# xmos_avb_brd_V4.net
KiCad netlist of a schematic drawn in EAGLE
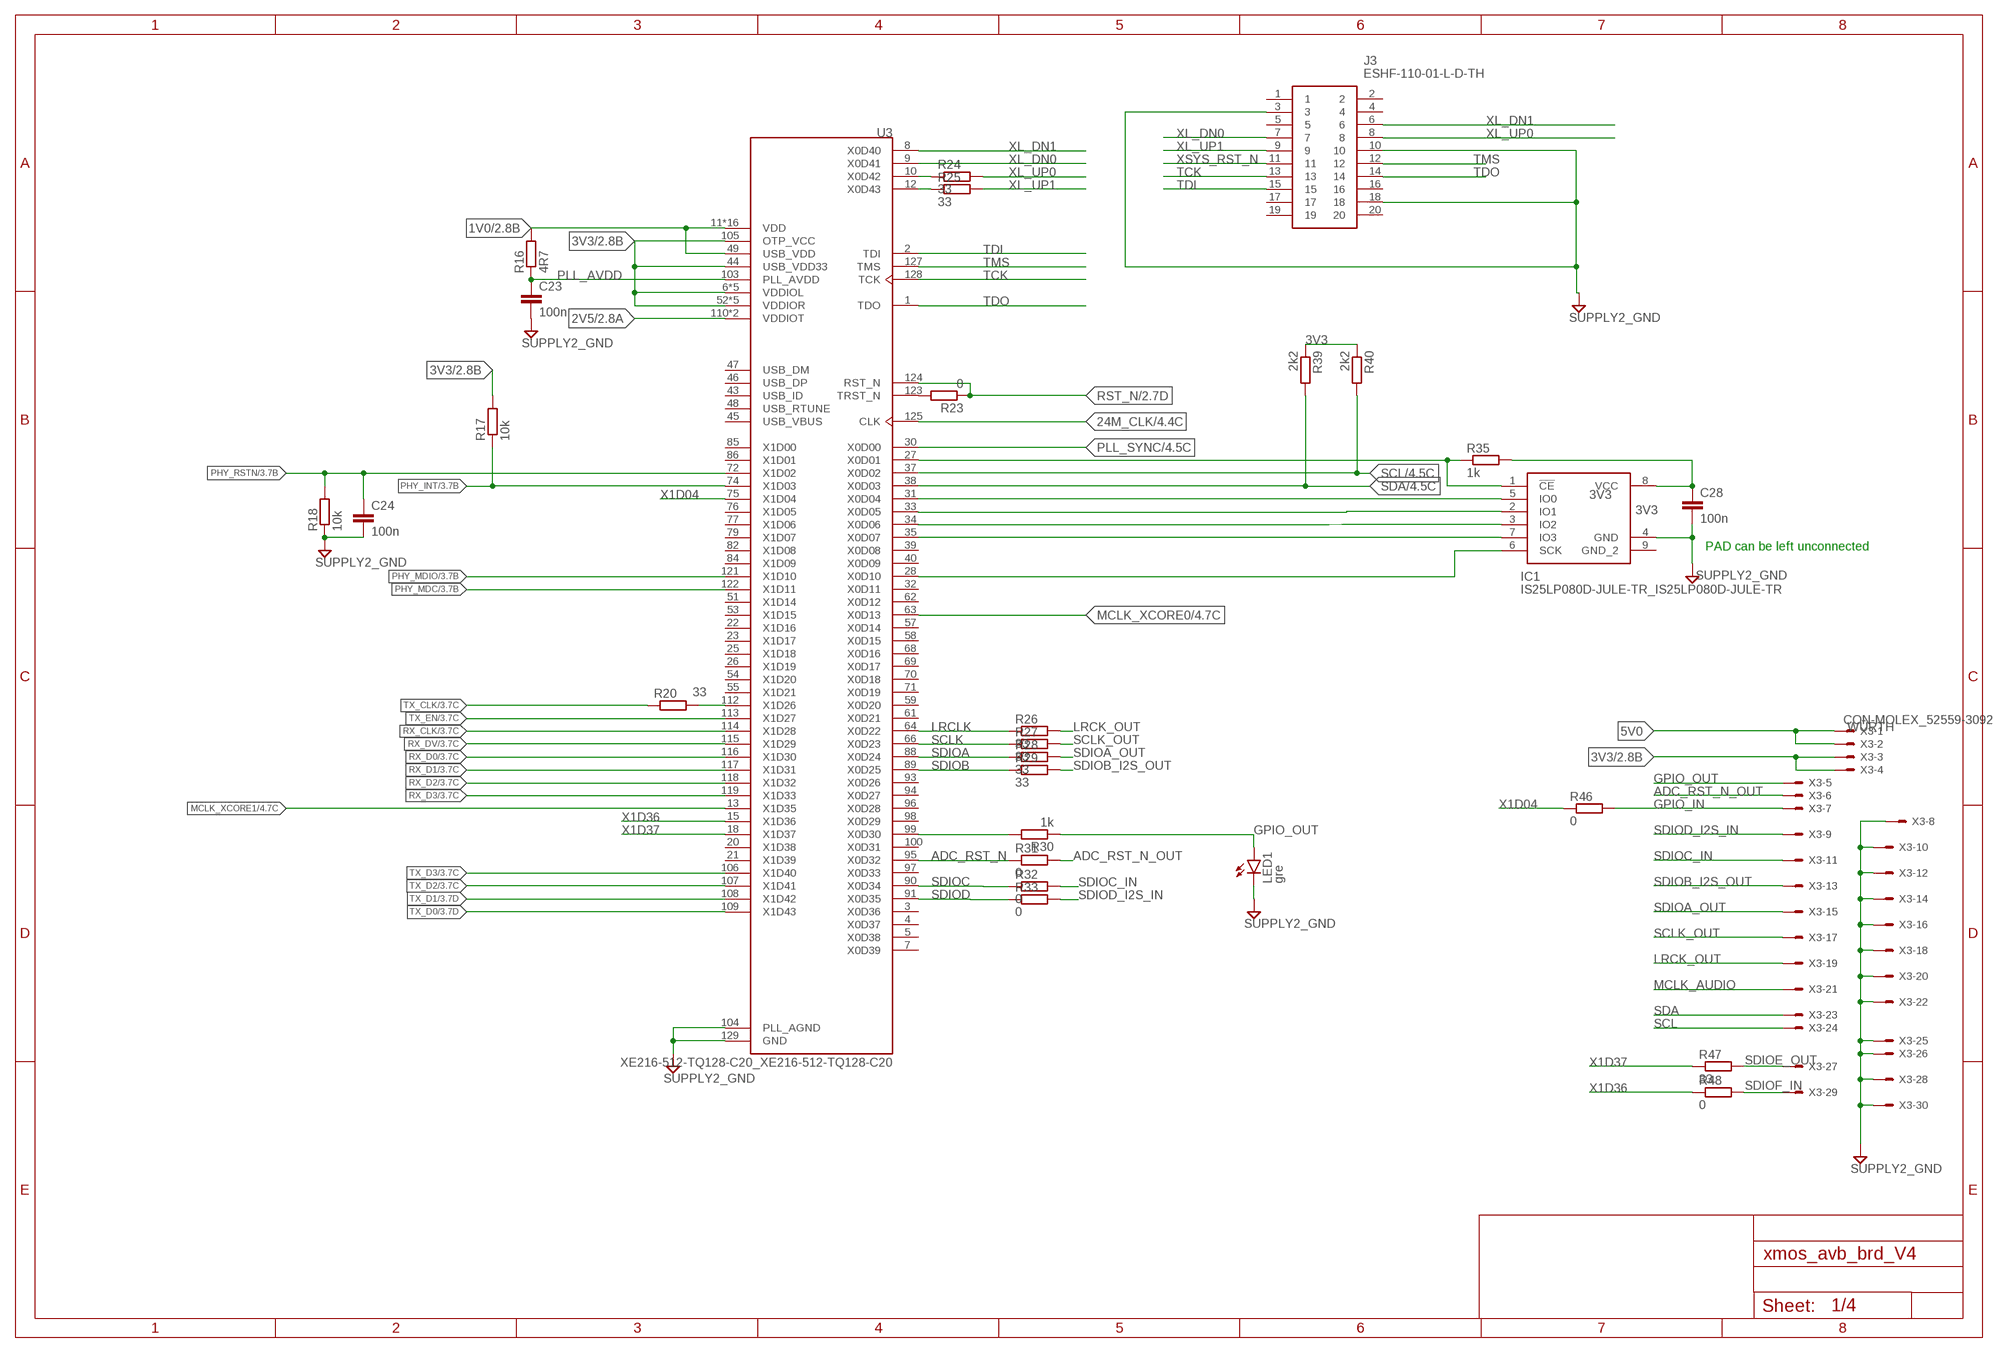
[diagram p0: schematic, sheet 1]
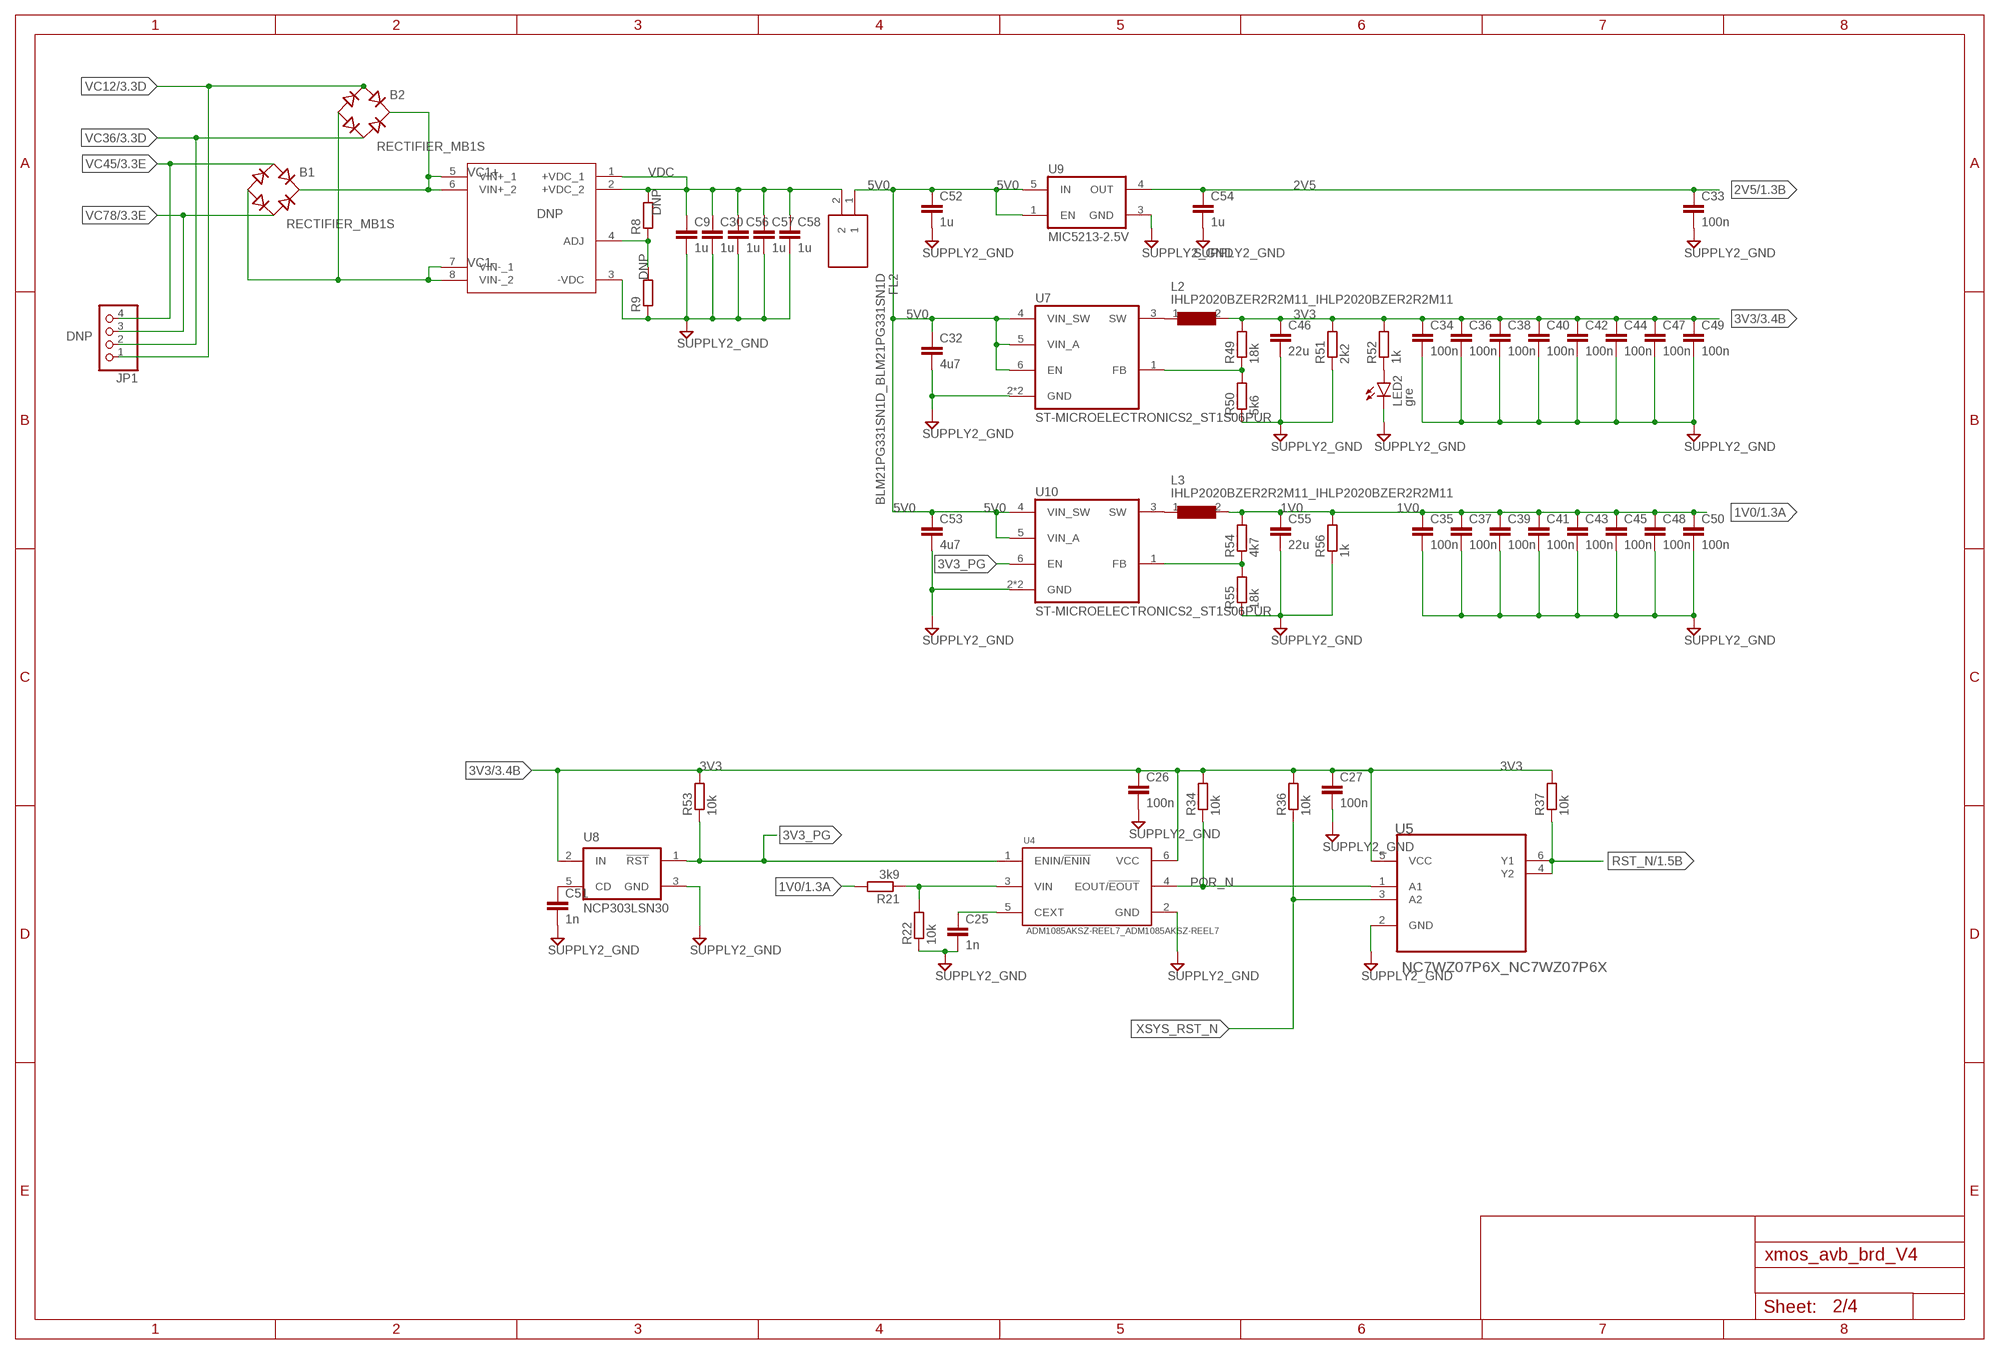
[diagram p1: schematic, sheet 2]
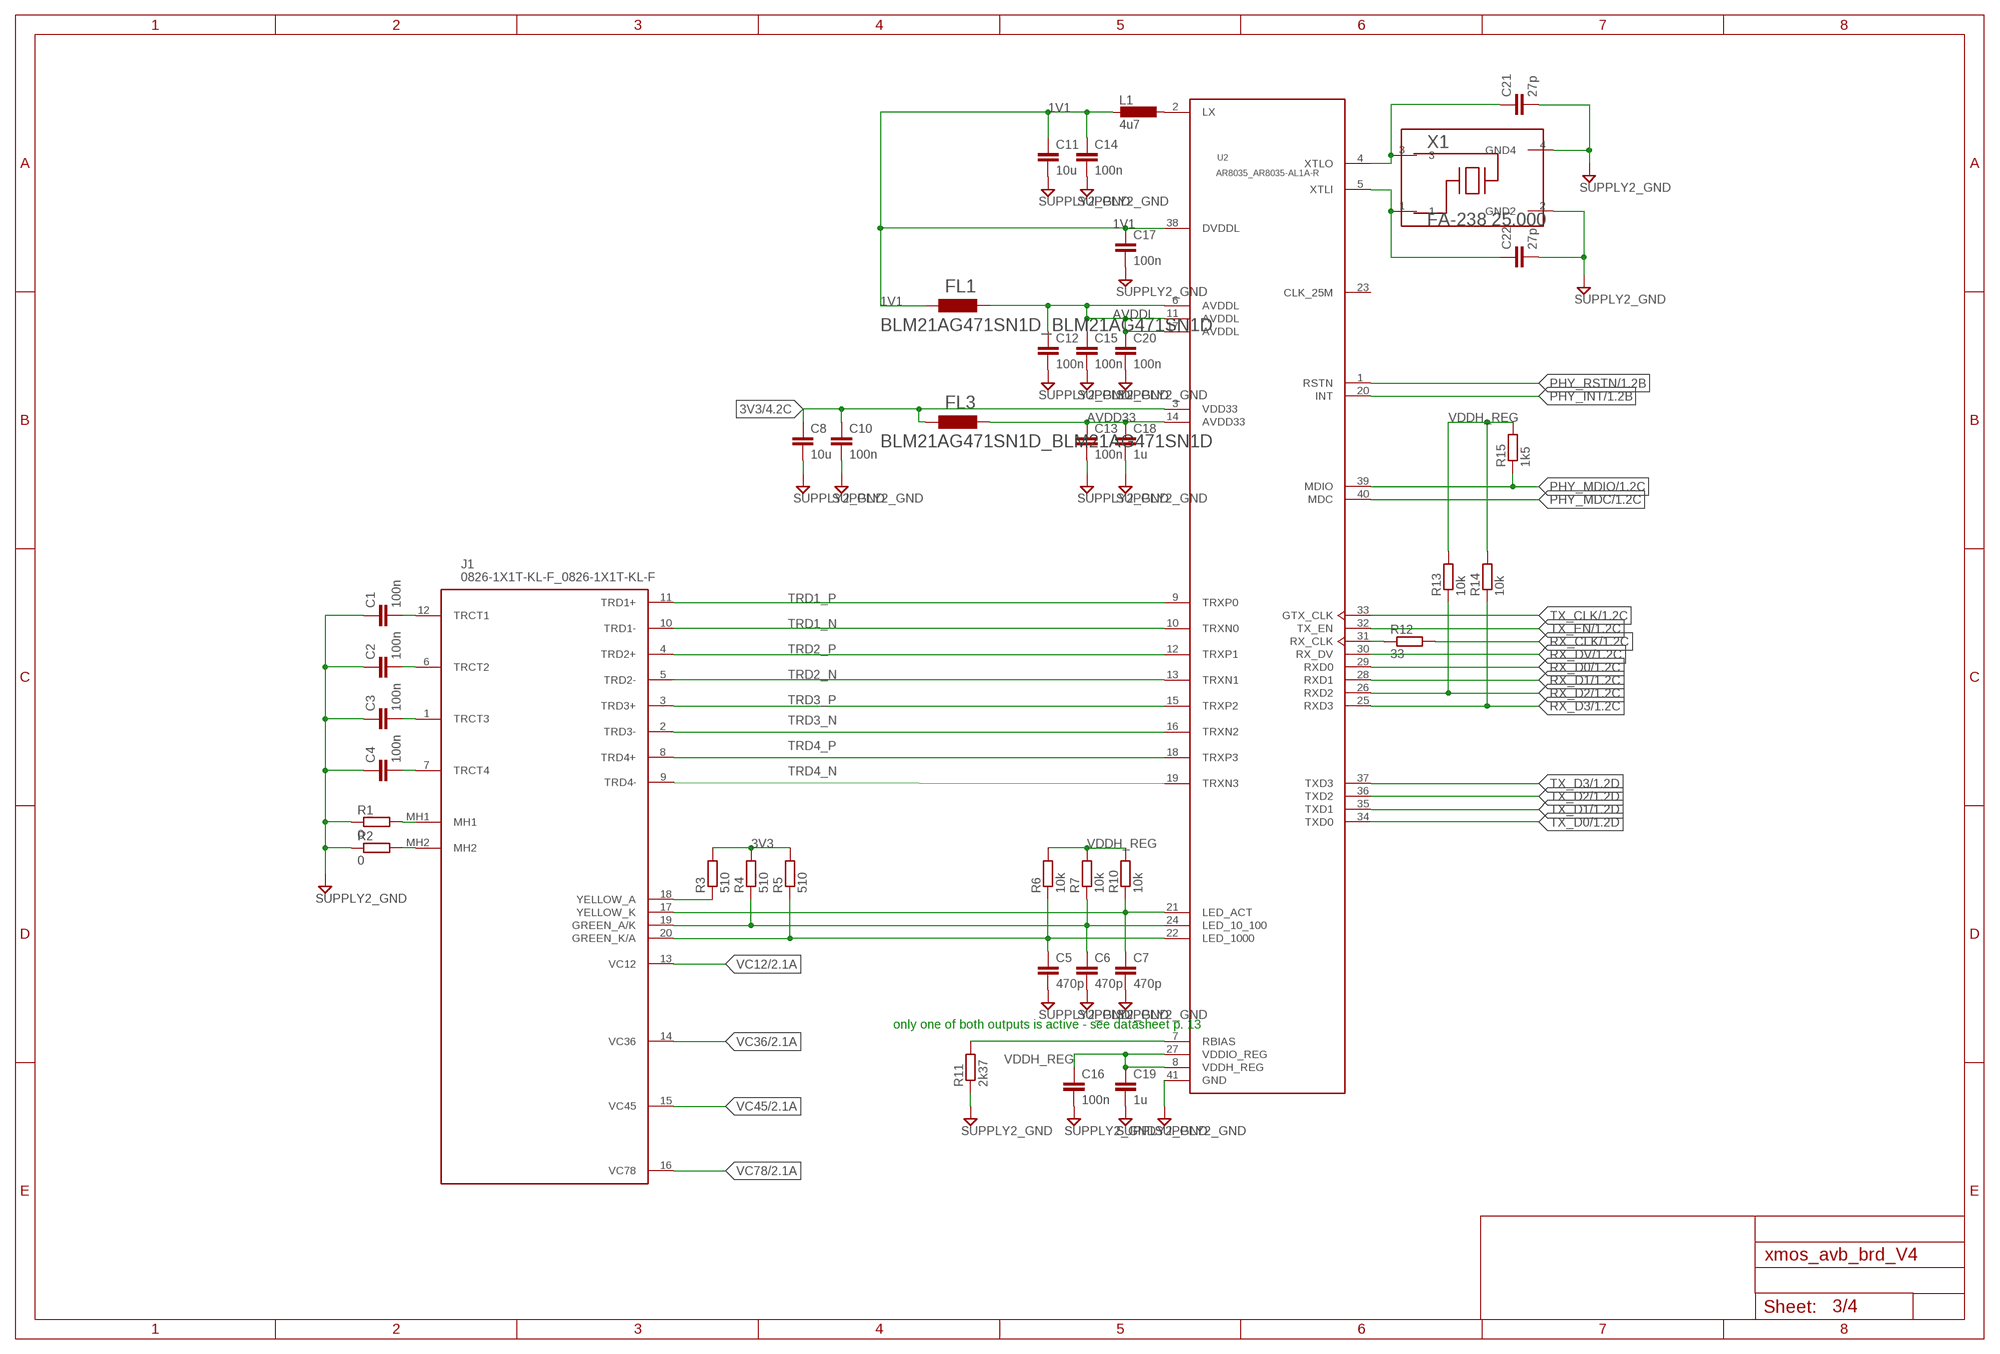
[diagram p2: schematic, sheet 3]
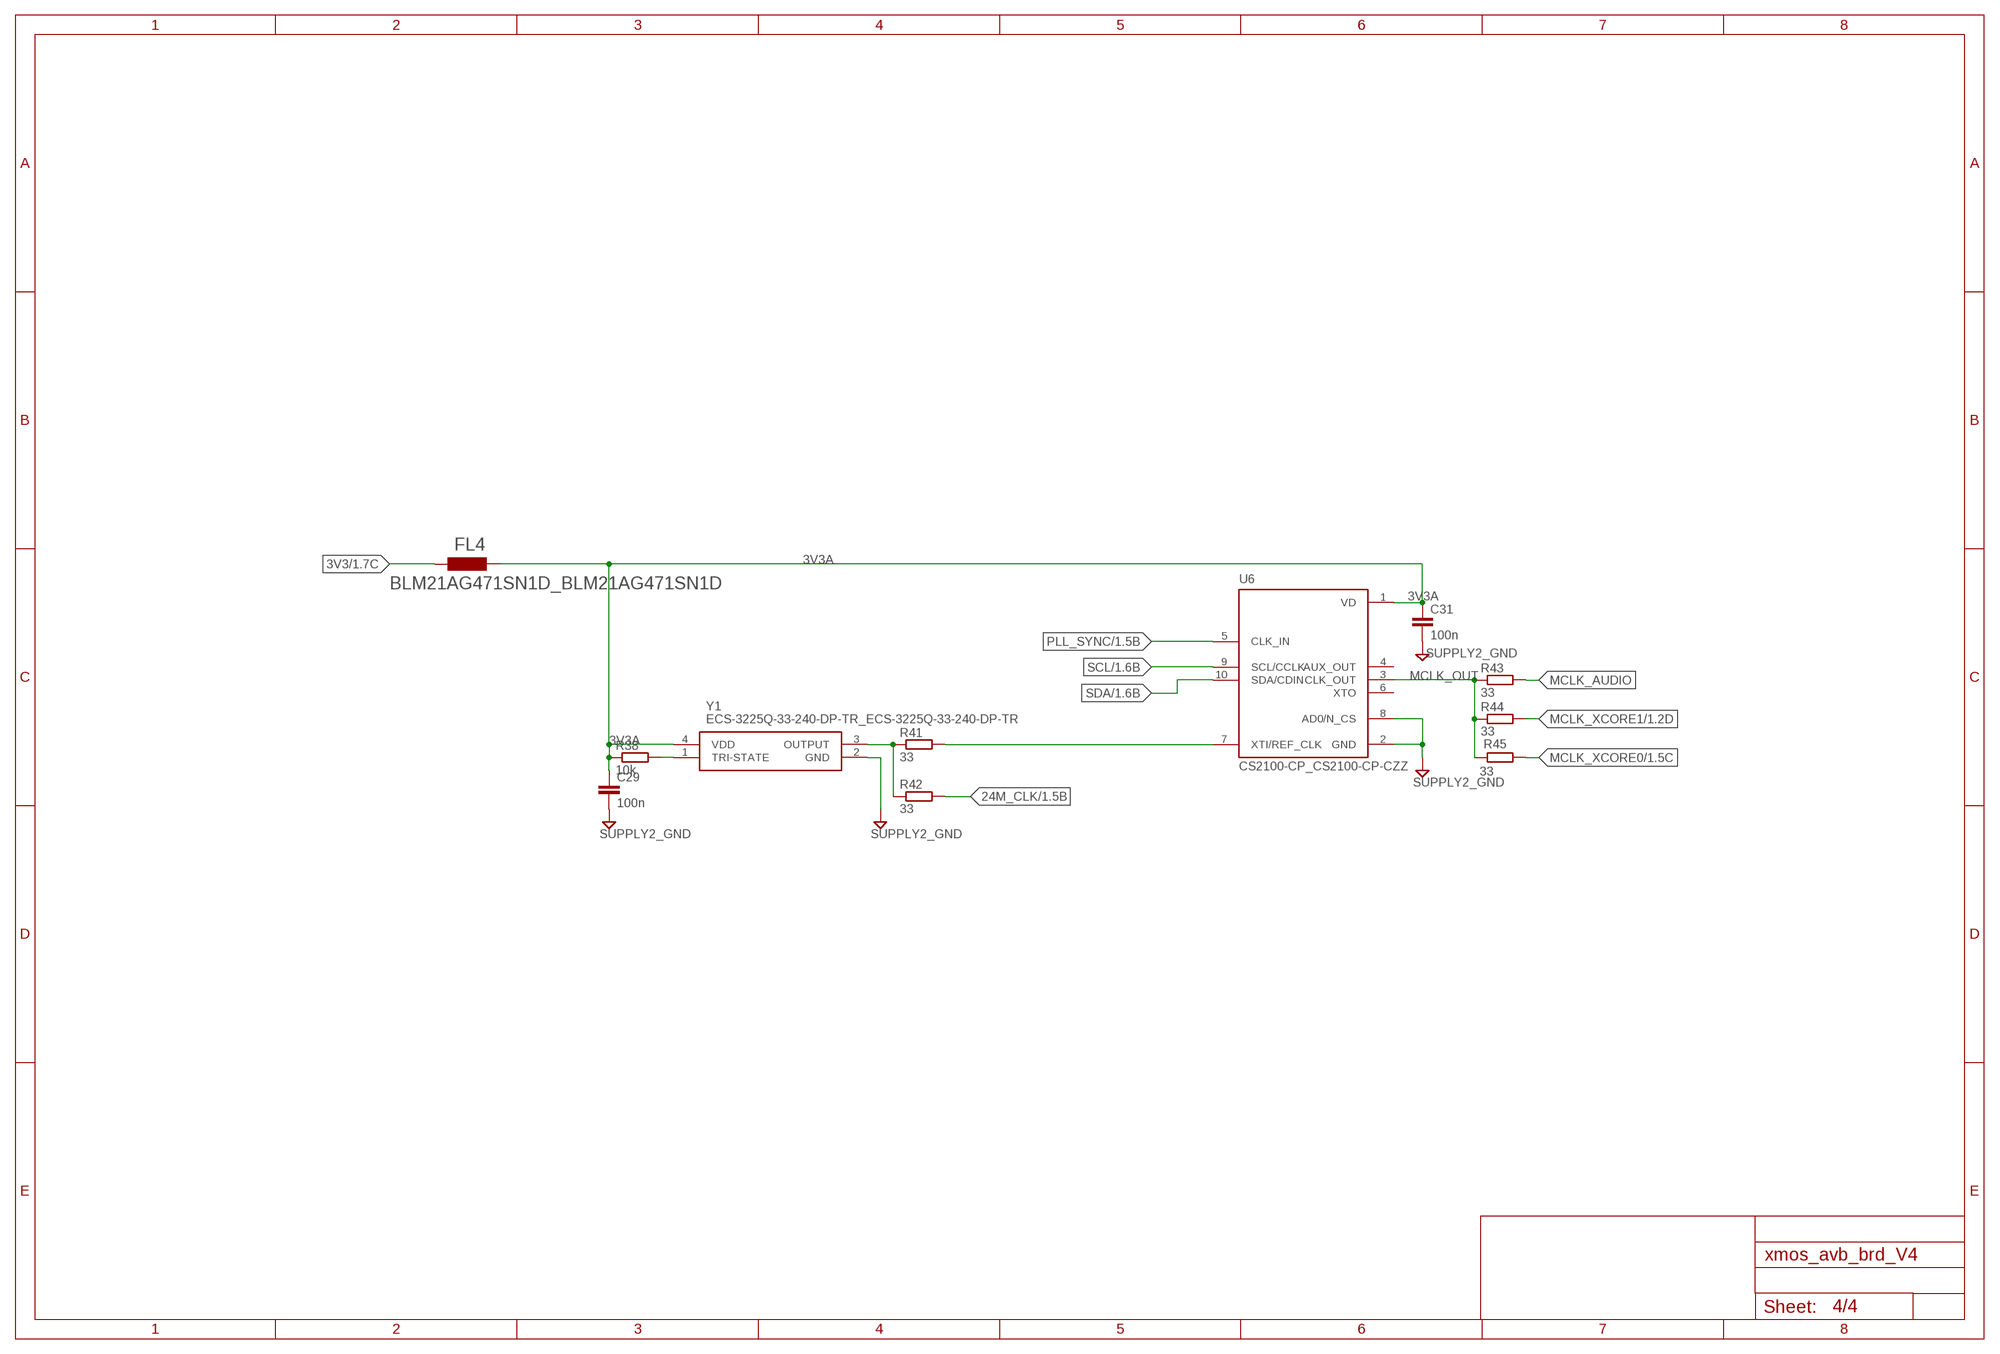
[diagram p3: schematic, sheet 4]

(export (version "E")
  (design (tool "Eeschema 10.0.6"))
  (components
    (comp (ref "B1")
      (value "RECTIFIER_MB1S")
      (footprint "eagle-import:RECTIFIER_SOIC-4")
      (libsource (lib "eagle-import") (part "RECTIFIER_MBS1"))
    )
    (comp (ref "B2")
      (value "RECTIFIER_MB1S")
      (footprint "eagle-import:RECTIFIER_SOIC-4")
      (libsource (lib "eagle-import") (part "RECTIFIER_MBS1"))
    )
    (comp (ref "C9")
      (value "1u")
      (footprint "eagle-import:RCL_C1206")
      (libsource (lib "eagle-import") (part "RCL_C-EUC1206"))
    )
    (comp (ref "C25")
      (value "1n")
      (footprint "eagle-import:RCL_C0402")
      (libsource (lib "eagle-import") (part "RCL_C-EUC0402"))
    )
    (comp (ref "C26")
      (value "100n")
      (footprint "eagle-import:RCL_C0402")
      (libsource (lib "eagle-import") (part "RCL_C-EUC0402"))
    )
    (comp (ref "C27")
      (value "100n")
      (footprint "eagle-import:RCL_C0402")
      (libsource (lib "eagle-import") (part "RCL_C-EUC0402"))
    )
    (comp (ref "C30")
      (value "1u")
      (footprint "eagle-import:RCL_C1206")
      (libsource (lib "eagle-import") (part "RCL_C-EUC1206"))
    )
    (comp (ref "C32")
      (value "4u7")
      (footprint "eagle-import:RCL_C1206")
      (libsource (lib "eagle-import") (part "RCL_C-EUC1206"))
    )
    (comp (ref "C33")
      (value "100n")
      (footprint "eagle-import:RCL_C0402")
      (libsource (lib "eagle-import") (part "RCL_C-EUC0402"))
    )
    (comp (ref "C34")
      (value "100n")
      (footprint "eagle-import:RCL_C0402")
      (libsource (lib "eagle-import") (part "RCL_C-EUC0402"))
    )
    (comp (ref "C35")
      (value "100n")
      (footprint "eagle-import:RCL_C0402")
      (libsource (lib "eagle-import") (part "RCL_C-EUC0402"))
    )
    (comp (ref "C36")
      (value "100n")
      (footprint "eagle-import:RCL_C0402")
      (libsource (lib "eagle-import") (part "RCL_C-EUC0402"))
    )
    (comp (ref "C37")
      (value "100n")
      (footprint "eagle-import:RCL_C0402")
      (libsource (lib "eagle-import") (part "RCL_C-EUC0402"))
    )
    (comp (ref "C38")
      (value "100n")
      (footprint "eagle-import:RCL_C0402")
      (libsource (lib "eagle-import") (part "RCL_C-EUC0402"))
    )
    (comp (ref "C39")
      (value "100n")
      (footprint "eagle-import:RCL_C0402")
      (libsource (lib "eagle-import") (part "RCL_C-EUC0402"))
    )
    (comp (ref "C40")
      (value "100n")
      (footprint "eagle-import:RCL_C0402")
      (libsource (lib "eagle-import") (part "RCL_C-EUC0402"))
    )
    (comp (ref "C41")
      (value "100n")
      (footprint "eagle-import:RCL_C0402")
      (libsource (lib "eagle-import") (part "RCL_C-EUC0402"))
    )
    (comp (ref "C42")
      (value "100n")
      (footprint "eagle-import:RCL_C0402")
      (libsource (lib "eagle-import") (part "RCL_C-EUC0402"))
    )
    (comp (ref "C43")
      (value "100n")
      (footprint "eagle-import:RCL_C0402")
      (libsource (lib "eagle-import") (part "RCL_C-EUC0402"))
    )
    (comp (ref "C44")
      (value "100n")
      (footprint "eagle-import:RCL_C0402")
      (libsource (lib "eagle-import") (part "RCL_C-EUC0402"))
    )
    (comp (ref "C45")
      (value "100n")
      (footprint "eagle-import:RCL_C0402")
      (libsource (lib "eagle-import") (part "RCL_C-EUC0402"))
    )
    (comp (ref "C46")
      (value "22u")
      (footprint "eagle-import:RCL_C1206")
      (libsource (lib "eagle-import") (part "RCL_C-EUC1206"))
    )
    (comp (ref "C47")
      (value "100n")
      (footprint "eagle-import:RCL_C0402")
      (libsource (lib "eagle-import") (part "RCL_C-EUC0402"))
    )
    (comp (ref "C48")
      (value "100n")
      (footprint "eagle-import:RCL_C0402")
      (libsource (lib "eagle-import") (part "RCL_C-EUC0402"))
    )
    (comp (ref "C49")
      (value "100n")
      (footprint "eagle-import:RCL_C0402")
      (libsource (lib "eagle-import") (part "RCL_C-EUC0402"))
    )
    (comp (ref "C50")
      (value "100n")
      (footprint "eagle-import:RCL_C0402")
      (libsource (lib "eagle-import") (part "RCL_C-EUC0402"))
    )
    (comp (ref "C51")
      (value "1n")
      (footprint "eagle-import:RCL_C0402")
      (libsource (lib "eagle-import") (part "RCL_C-EUC0402"))
    )
    (comp (ref "C52")
      (value "1u")
      (footprint "eagle-import:RCL_C1206")
      (libsource (lib "eagle-import") (part "RCL_C-EUC1206"))
    )
    (comp (ref "C53")
      (value "4u7")
      (footprint "eagle-import:RCL_C1206")
      (libsource (lib "eagle-import") (part "RCL_C-EUC1206"))
    )
    (comp (ref "C54")
      (value "1u")
      (footprint "eagle-import:RCL_C1206")
      (libsource (lib "eagle-import") (part "RCL_C-EUC1206"))
    )
    (comp (ref "C55")
      (value "22u")
      (footprint "eagle-import:RCL_C1206")
      (libsource (lib "eagle-import") (part "RCL_C-EUC1206"))
    )
    (comp (ref "C56")
      (value "1u")
      (footprint "eagle-import:RCL_C1206")
      (libsource (lib "eagle-import") (part "RCL_C-EUC1206"))
    )
    (comp (ref "C57")
      (value "1u")
      (footprint "eagle-import:RCL_C1206")
      (libsource (lib "eagle-import") (part "RCL_C-EUC1206"))
    )
    (comp (ref "C58")
      (value "1u")
      (footprint "eagle-import:RCL_C1206")
      (libsource (lib "eagle-import") (part "RCL_C-EUC1206"))
    )
    (comp (ref "FL2")
      (value "BLM21PG331SN1D_BLM21PG331SN1D")
      (footprint "eagle-import:BLM21PG331SN1D_BEADC2012X105N")
      (fields
        (field (name "MANUFACTURER_PART_NUMBER") "BLM21PG331SN1D")
        (field (name "MOUSER_PART_NUMBER") "81-BLM21P331SG")
      )
      (libsource (lib "eagle-import") (part "BLM21PG331SN1D_BLM21PG331SN1D"))
    )
    (comp (ref "JP1")
      (value "PINHEAD_PINHD-1X4")
      (footprint "eagle-import:PINHEAD_1X04")
      (fields (field (name "DNP") "DNP"))
      (libsource (lib "eagle-import") (part "PINHEAD_PINHD-1X4"))
    )
    (comp (ref "L2")
      (value "IHLP2020BZER2R2M11_IHLP2020BZER2R2M11")
      (footprint "eagle-import:IHLP2020BZER2R2M11_INDPM5552X200N")
      (fields
        (field (name "MANUFACTURER_PART_NUMBER") "IHLP2020BZER2R2M11")
        (field (name "MOUSER_PART_NUMBER") "70-IHLP2020BZER2R2M1")
      )
      (libsource (lib "eagle-import") (part "IHLP2020BZER2R2M11_IHLP2020BZER2R2M11"))
    )
    (comp (ref "L3")
      (value "IHLP2020BZER2R2M11_IHLP2020BZER2R2M11")
      (footprint "eagle-import:IHLP2020BZER2R2M11_INDPM5552X200N")
      (fields
        (field (name "MANUFACTURER_PART_NUMBER") "IHLP2020BZER2R2M11")
        (field (name "MOUSER_PART_NUMBER") "70-IHLP2020BZER2R2M1")
      )
      (libsource (lib "eagle-import") (part "IHLP2020BZER2R2M11_IHLP2020BZER2R2M11"))
    )
    (comp (ref "LED2")
      (value "gre")
      (footprint "eagle-import:LED_CHIP-LED0603")
      (libsource (lib "eagle-import") (part "LED_LEDCHIP-LED0603"))
    )
    (comp (ref "R8")
      (value "RCL_R-EU_R0402")
      (footprint "eagle-import:RCL_R0402")
      (fields (field (name "DNP") "DNP"))
      (libsource (lib "eagle-import") (part "RCL_R-EU_R0402"))
    )
    (comp (ref "R9")
      (value "RCL_R-EU_R0402")
      (footprint "eagle-import:RCL_R0402")
      (fields (field (name "DNP") "DNP"))
      (libsource (lib "eagle-import") (part "RCL_R-EU_R0402"))
    )
    (comp (ref "R21")
      (value "3k9")
      (footprint "eagle-import:RCL_R0402")
      (libsource (lib "eagle-import") (part "RCL_R-EU_R0402"))
    )
    (comp (ref "R22")
      (value "10k")
      (footprint "eagle-import:RCL_R0402")
      (libsource (lib "eagle-import") (part "RCL_R-EU_R0402"))
    )
    (comp (ref "R34")
      (value "10k")
      (footprint "eagle-import:RCL_R0402")
      (libsource (lib "eagle-import") (part "RCL_R-EU_R0402"))
    )
    (comp (ref "R36")
      (value "10k")
      (footprint "eagle-import:RCL_R0402")
      (libsource (lib "eagle-import") (part "RCL_R-EU_R0402"))
    )
    (comp (ref "R37")
      (value "10k")
      (footprint "eagle-import:RCL_R0402")
      (libsource (lib "eagle-import") (part "RCL_R-EU_R0402"))
    )
    (comp (ref "R49")
      (value "18k")
      (footprint "eagle-import:RCL_R0402")
      (libsource (lib "eagle-import") (part "RCL_R-EU_R0402"))
    )
    (comp (ref "R50")
      (value "5k6")
      (footprint "eagle-import:RCL_R0402")
      (libsource (lib "eagle-import") (part "RCL_R-EU_R0402"))
    )
    (comp (ref "R51")
      (value "2k2")
      (footprint "eagle-import:RCL_R0402")
      (libsource (lib "eagle-import") (part "RCL_R-EU_R0402"))
    )
    (comp (ref "R52")
      (value "1k")
      (footprint "eagle-import:RCL_R0402")
      (libsource (lib "eagle-import") (part "RCL_R-EU_R0402"))
    )
    (comp (ref "R53")
      (value "10k")
      (footprint "eagle-import:RCL_R0402")
      (libsource (lib "eagle-import") (part "RCL_R-EU_R0402"))
    )
    (comp (ref "R54")
      (value "4k7")
      (footprint "eagle-import:RCL_R0402")
      (libsource (lib "eagle-import") (part "RCL_R-EU_R0402"))
    )
    (comp (ref "R55")
      (value "18k")
      (footprint "eagle-import:RCL_R0402")
      (libsource (lib "eagle-import") (part "RCL_R-EU_R0402"))
    )
    (comp (ref "R56")
      (value "1k")
      (footprint "eagle-import:RCL_R0402")
      (libsource (lib "eagle-import") (part "RCL_R-EU_R0402"))
    )
    (comp (ref "U1")
      (value "AG9900_AG9905LP")
      (footprint "eagle-import:AG9900_AG9900LP")
      (fields (field (name "MF") "Silvertel") (field (name "MP") "AG9905LP") (field (name "DNP") "DNP"))
      (libsource (lib "eagle-import") (part "AG9900_AG9905LP"))
    )
    (comp (ref "U4")
      (value "ADM1085AKSZ-REEL7_ADM1085AKSZ-REEL7")
      (footprint "eagle-import:ADM1085AKSZ-REEL7_SOP65P210X95-6N")
      (fields (field (name "MF") "Analog Devices") (field (name "MP") "ADM1085AKSZ-REEL7"))
      (libsource (lib "eagle-import") (part "ADM1085AKSZ-REEL7_ADM1085AKSZ-REEL7"))
    )
    (comp (ref "U5")
      (value "NC7WZ07P6X_NC7WZ07P6X")
      (footprint "eagle-import:NC7WZ07P6X_SOT65P210X110-6N")
      (fields (field (name "MF") "ON Semiconductor") (field (name "MP") "NC7WZ07P6X"))
      (libsource (lib "eagle-import") (part "NC7WZ07P6X_NC7WZ07P6X"))
    )
    (comp (ref "U7")
      (value "ST-MICROELECTRONICS2_ST1S06PUR")
      (footprint "eagle-import:ST-MICROELECTRONICS2_DFN6")
      (libsource (lib "eagle-import") (part "ST-MICROELECTRONICS2_ST1S06PUR"))
    )
    (comp (ref "U8")
      (value "NCP303LSN30")
      (footprint "eagle-import:ON-SEMI_SOT23-5")
      (libsource (lib "eagle-import") (part "ON-SEMI_NCP303"))
    )
    (comp (ref "U9")
      (value "MIC5213-2.5V")
      (footprint "eagle-import:MICREL2_SC70-5")
      (libsource (lib "eagle-import") (part "MICREL2_MIC5213"))
    )
    (comp (ref "U10")
      (value "ST-MICROELECTRONICS2_ST1S06PUR")
      (footprint "eagle-import:ST-MICROELECTRONICS2_DFN6")
      (libsource (lib "eagle-import") (part "ST-MICROELECTRONICS2_ST1S06PUR"))
    )
    (comp (ref "C1")
      (value "100n")
      (footprint "eagle-import:RCL_C0402")
      (libsource (lib "eagle-import") (part "RCL_C-EUC0402"))
    )
    (comp (ref "C2")
      (value "100n")
      (footprint "eagle-import:RCL_C0402")
      (libsource (lib "eagle-import") (part "RCL_C-EUC0402"))
    )
    (comp (ref "C3")
      (value "100n")
      (footprint "eagle-import:RCL_C0402")
      (libsource (lib "eagle-import") (part "RCL_C-EUC0402"))
    )
    (comp (ref "C4")
      (value "100n")
      (footprint "eagle-import:RCL_C0402")
      (libsource (lib "eagle-import") (part "RCL_C-EUC0402"))
    )
    (comp (ref "C5")
      (value "470p")
      (footprint "eagle-import:RCL_C0402")
      (libsource (lib "eagle-import") (part "RCL_C-EUC0402"))
    )
    (comp (ref "C6")
      (value "470p")
      (footprint "eagle-import:RCL_C0402")
      (libsource (lib "eagle-import") (part "RCL_C-EUC0402"))
    )
    (comp (ref "C7")
      (value "470p")
      (footprint "eagle-import:RCL_C0402")
      (libsource (lib "eagle-import") (part "RCL_C-EUC0402"))
    )
    (comp (ref "C8")
      (value "10u")
      (footprint "eagle-import:RCL_C1206")
      (libsource (lib "eagle-import") (part "RCL_C-EUC1206"))
    )
    (comp (ref "C10")
      (value "100n")
      (footprint "eagle-import:RCL_C0402")
      (libsource (lib "eagle-import") (part "RCL_C-EUC0402"))
    )
    (comp (ref "C11")
      (value "10u")
      (footprint "eagle-import:RCL_C1206")
      (libsource (lib "eagle-import") (part "RCL_C-EUC1206"))
    )
    (comp (ref "C12")
      (value "100n")
      (footprint "eagle-import:RCL_C0402")
      (libsource (lib "eagle-import") (part "RCL_C-EUC0402"))
    )
    (comp (ref "C13")
      (value "100n")
      (footprint "eagle-import:RCL_C0402")
      (libsource (lib "eagle-import") (part "RCL_C-EUC0402"))
    )
    (comp (ref "C14")
      (value "100n")
      (footprint "eagle-import:RCL_C0402")
      (libsource (lib "eagle-import") (part "RCL_C-EUC0402"))
    )
    (comp (ref "C15")
      (value "100n")
      (footprint "eagle-import:RCL_C0402")
      (libsource (lib "eagle-import") (part "RCL_C-EUC0402"))
    )
    (comp (ref "C16")
      (value "100n")
      (footprint "eagle-import:RCL_C0402")
      (libsource (lib "eagle-import") (part "RCL_C-EUC0402"))
    )
    (comp (ref "C17")
      (value "100n")
      (footprint "eagle-import:RCL_C0402")
      (libsource (lib "eagle-import") (part "RCL_C-EUC0402"))
    )
    (comp (ref "C18")
      (value "1u")
      (footprint "eagle-import:RCL_C1206")
      (libsource (lib "eagle-import") (part "RCL_C-EUC1206"))
    )
    (comp (ref "C19")
      (value "1u")
      (footprint "eagle-import:RCL_C1206")
      (libsource (lib "eagle-import") (part "RCL_C-EUC1206"))
    )
    (comp (ref "C20")
      (value "100n")
      (footprint "eagle-import:RCL_C0402")
      (libsource (lib "eagle-import") (part "RCL_C-EUC0402"))
    )
    (comp (ref "C21")
      (value "27p")
      (footprint "eagle-import:RCL_C0402")
      (libsource (lib "eagle-import") (part "RCL_C-EUC0402"))
    )
    (comp (ref "C22")
      (value "27p")
      (footprint "eagle-import:RCL_C0402")
      (libsource (lib "eagle-import") (part "RCL_C-EUC0402"))
    )
    (comp (ref "FL1")
      (value "BLM21AG471SN1D_BLM21AG471SN1D")
      (footprint "eagle-import:BLM21AG471SN1D_BEADC2012X105N")
      (fields (field (name "MF") "Murata Electronics") (field (name "MP") "BLM21AG471SN1D"))
      (libsource (lib "eagle-import") (part "BLM21AG471SN1D_BLM21AG471SN1D"))
    )
    (comp (ref "FL3")
      (value "BLM21AG471SN1D_BLM21AG471SN1D")
      (footprint "eagle-import:BLM21AG471SN1D_BEADC2012X105N")
      (fields (field (name "MF") "Murata Electronics") (field (name "MP") "BLM21AG471SN1D"))
      (libsource (lib "eagle-import") (part "BLM21AG471SN1D_BLM21AG471SN1D"))
    )
    (comp (ref "J1")
      (value "0826-1X1T-KL-F_0826-1X1T-KL-F")
      (footprint "eagle-import:0826-1X1T-KL-F_08261X1TKLF")
      (fields
        (field (name "MANUFACTURER_PART_NUMBER") "0826-1X1T-KL-F")
        (field (name "MOUSER_PART_NUMBER") "530-0826-1X1T-KL-F")
      )
      (libsource (lib "eagle-import") (part "0826-1X1T-KL-F_0826-1X1T-KL-F"))
    )
    (comp (ref "L1")
      (value "4u7")
      (footprint "eagle-import:RCL_L2012C")
      (libsource (lib "eagle-import") (part "RCL_L-EUL2012C"))
    )
    (comp (ref "R1")
      (value "0")
      (footprint "eagle-import:RCL_R0402")
      (libsource (lib "eagle-import") (part "RCL_R-EU_R0402"))
    )
    (comp (ref "R2")
      (value "0")
      (footprint "eagle-import:RCL_R0402")
      (libsource (lib "eagle-import") (part "RCL_R-EU_R0402"))
    )
    (comp (ref "R3")
      (value "510")
      (footprint "eagle-import:RCL_R0402")
      (libsource (lib "eagle-import") (part "RCL_R-EU_R0402"))
    )
    (comp (ref "R4")
      (value "510")
      (footprint "eagle-import:RCL_R0402")
      (libsource (lib "eagle-import") (part "RCL_R-EU_R0402"))
    )
    (comp (ref "R5")
      (value "510")
      (footprint "eagle-import:RCL_R0402")
      (libsource (lib "eagle-import") (part "RCL_R-EU_R0402"))
    )
    (comp (ref "R6")
      (value "10k")
      (footprint "eagle-import:RCL_R0402")
      (libsource (lib "eagle-import") (part "RCL_R-EU_R0402"))
    )
    (comp (ref "R7")
      (value "10k")
      (footprint "eagle-import:RCL_R0402")
      (libsource (lib "eagle-import") (part "RCL_R-EU_R0402"))
    )
    (comp (ref "R10")
      (value "10k")
      (footprint "eagle-import:RCL_R0402")
      (libsource (lib "eagle-import") (part "RCL_R-EU_R0402"))
    )
    (comp (ref "R11")
      (value "2k37")
      (footprint "eagle-import:RCL_R0402")
      (libsource (lib "eagle-import") (part "RCL_R-EU_R0402"))
    )
    (comp (ref "R12")
      (value "33")
      (footprint "eagle-import:RCL_R0402")
      (libsource (lib "eagle-import") (part "RCL_R-EU_R0402"))
    )
    (comp (ref "R13")
      (value "10k")
      (footprint "eagle-import:RCL_R0402")
      (libsource (lib "eagle-import") (part "RCL_R-EU_R0402"))
    )
    (comp (ref "R14")
      (value "10k")
      (footprint "eagle-import:RCL_R0402")
      (libsource (lib "eagle-import") (part "RCL_R-EU_R0402"))
    )
    (comp (ref "R15")
      (value "1k5")
      (footprint "eagle-import:RCL_R0402")
      (libsource (lib "eagle-import") (part "RCL_R-EU_R0402"))
    )
    (comp (ref "U2")
      (value "AR8035_AR8035-AL1A-R")
      (footprint "eagle-import:AR8035_QFN40P500X500X75-41N")
      (fields (field (name "MF") "Qualcomm") (field (name "MP") "AR8035-AL1A-R"))
      (libsource (lib "eagle-import") (part "AR8035_AR8035-AL1A-R"))
    )
    (comp (ref "X1")
      (value "FA-238 25.000")
      (footprint "eagle-import:FA-238_OSCCC320X250X70-4N")
      (fields
        (field (name "MANUFACTURER_PART_NUMBER") "FA-238 25.0000MB-C3 ")
        (field (name "MF") "Epson")
        (field (name "MP") "FA-238")
      )
      (libsource (lib "eagle-import") (part "FA-238_FA-238"))
    )
    (comp (ref "C23")
      (value "100n")
      (footprint "eagle-import:RCL_C0402")
      (libsource (lib "eagle-import") (part "RCL_C-EUC0402"))
    )
    (comp (ref "C24")
      (value "100n")
      (footprint "eagle-import:RCL_C0402")
      (libsource (lib "eagle-import") (part "RCL_C-EUC0402"))
    )
    (comp (ref "C28")
      (value "100n")
      (footprint "eagle-import:RCL_C0402")
      (libsource (lib "eagle-import") (part "RCL_C-EUC0402"))
    )
    (comp (ref "IC1")
      (value "IS25LP080D-JULE-TR_IS25LP080D-JULE-TR")
      (footprint "eagle-import:IS25LP080D-JULE-TR_SON50P300X200X55-9N")
      (fields (field (name "MANUFACTURER_PART_NUMBER") "IS25LP080D-JULE-TR"))
      (libsource (lib "eagle-import") (part "IS25LP080D-JULE-TR_IS25LP080D-JULE-TR"))
    )
    (comp (ref "J3")
      (value "ESHF-110-01-L-D-TH")
      (footprint "eagle-import:SHDR20W41P127_2X10_1905X559X54")
      (fields (field (name "MOUSER_PART_NUMBER") "200-ESHF11001LDTH"))
      (libsource (lib "eagle-import") (part "ESHF-110-01-L-D-TH"))
    )
    (comp (ref "LED1")
      (value "gre")
      (footprint "eagle-import:LED_CHIP-LED0603")
      (libsource (lib "eagle-import") (part "LED_LEDCHIP-LED0603"))
    )
    (comp (ref "R16")
      (value "4R7")
      (footprint "eagle-import:RCL_R0402")
      (libsource (lib "eagle-import") (part "RCL_R-EU_R0402"))
    )
    (comp (ref "R17")
      (value "10k")
      (footprint "eagle-import:RCL_R0402")
      (libsource (lib "eagle-import") (part "RCL_R-EU_R0402"))
    )
    (comp (ref "R18")
      (value "10k")
      (footprint "eagle-import:RCL_R0402")
      (libsource (lib "eagle-import") (part "RCL_R-EU_R0402"))
    )
    (comp (ref "R20")
      (value "33")
      (footprint "eagle-import:RCL_R0402")
      (libsource (lib "eagle-import") (part "RCL_R-EU_R0402"))
    )
    (comp (ref "R23")
      (value "0")
      (footprint "eagle-import:RCL_R0402")
      (libsource (lib "eagle-import") (part "RCL_R-EU_R0402"))
    )
    (comp (ref "R24")
      (value "33")
      (footprint "eagle-import:RCL_R0402")
      (libsource (lib "eagle-import") (part "RCL_R-EU_R0402"))
    )
    (comp (ref "R25")
      (value "33")
      (footprint "eagle-import:RCL_R0402")
      (libsource (lib "eagle-import") (part "RCL_R-EU_R0402"))
    )
    (comp (ref "R26")
      (value "33")
      (footprint "eagle-import:RCL_R0402")
      (libsource (lib "eagle-import") (part "RCL_R-EU_R0402"))
    )
    (comp (ref "R27")
      (value "33")
      (footprint "eagle-import:RCL_R0402")
      (libsource (lib "eagle-import") (part "RCL_R-EU_R0402"))
    )
    (comp (ref "R28")
      (value "33")
      (footprint "eagle-import:RCL_R0402")
      (libsource (lib "eagle-import") (part "RCL_R-EU_R0402"))
    )
    (comp (ref "R29")
      (value "33")
      (footprint "eagle-import:RCL_R0402")
      (libsource (lib "eagle-import") (part "RCL_R-EU_R0402"))
    )
    (comp (ref "R30")
      (value "1k")
      (footprint "eagle-import:RCL_R0402")
      (libsource (lib "eagle-import") (part "RCL_R-EU_R0402"))
    )
    (comp (ref "R31")
      (value "0")
      (footprint "eagle-import:RCL_R0402")
      (libsource (lib "eagle-import") (part "RCL_R-EU_R0402"))
    )
    (comp (ref "R32")
      (value "0")
      (footprint "eagle-import:RCL_R0402")
      (libsource (lib "eagle-import") (part "RCL_R-EU_R0402"))
    )
    (comp (ref "R33")
      (value "0")
      (footprint "eagle-import:RCL_R0402")
      (libsource (lib "eagle-import") (part "RCL_R-EU_R0402"))
    )
    (comp (ref "R35")
      (value "1k")
      (footprint "eagle-import:RCL_R0402")
      (libsource (lib "eagle-import") (part "RCL_R-EU_R0402"))
    )
    (comp (ref "R39")
      (value "2k2")
      (footprint "eagle-import:RCL_R0402")
      (libsource (lib "eagle-import") (part "RCL_R-EU_R0402"))
    )
    (comp (ref "R40")
      (value "2k2")
      (footprint "eagle-import:RCL_R0402")
      (libsource (lib "eagle-import") (part "RCL_R-EU_R0402"))
    )
    (comp (ref "R46")
      (value "0")
      (footprint "eagle-import:RCL_R0402")
      (libsource (lib "eagle-import") (part "RCL_R-EU_R0402"))
    )
    (comp (ref "R47")
      (value "33")
      (footprint "eagle-import:RCL_R0402")
      (libsource (lib "eagle-import") (part "RCL_R-EU_R0402"))
    )
    (comp (ref "R48")
      (value "0")
      (footprint "eagle-import:RCL_R0402")
      (libsource (lib "eagle-import") (part "RCL_R-EU_R0402"))
    )
    (comp (ref "U3")
      (value "XE216-512-TQ128-C20_XE216-512-TQ128-C20")
      (footprint "eagle-import:XE216-512-TQ128-C20_QFP40P1600X1600X120-129N")
      (fields (field (name "MF") "XMOS") (field (name "MP") "XE216-512-TQ128-C20"))
      (libsource (lib "eagle-import") (part "XE216-512-TQ128-C20_XE216-512-TQ128-C20"))
    )
    (comp (ref "X3")
      (value "CON-MOLEX_52559-3092")
      (footprint "eagle-import:CON-MOLEX_52559-3092")
      (fields
        (field (name "MF") "MOLEX")
        (field (name "MPN") "52559-3072")
        (field (name "MF_1") "WÜRTH")
        (field (name "MPN_1") "687330124422")
      )
      (libsource (lib "eagle-import") (part "CON-MOLEX_52559-3092"))
    )
    (comp (ref "C29")
      (value "100n")
      (footprint "eagle-import:RCL_C0402")
      (libsource (lib "eagle-import") (part "RCL_C-EUC0402"))
    )
    (comp (ref "C31")
      (value "100n")
      (footprint "eagle-import:RCL_C0402")
      (libsource (lib "eagle-import") (part "RCL_C-EUC0402"))
    )
    (comp (ref "FL4")
      (value "BLM21AG471SN1D_BLM21AG471SN1D")
      (footprint "eagle-import:BLM21AG471SN1D_BEADC2012X105N")
      (fields (field (name "MF") "Murata Electronics") (field (name "MP") "BLM21AG471SN1D"))
      (libsource (lib "eagle-import") (part "BLM21AG471SN1D_BLM21AG471SN1D"))
    )
    (comp (ref "R38")
      (value "10k")
      (footprint "eagle-import:RCL_R0402")
      (libsource (lib "eagle-import") (part "RCL_R-EU_R0402"))
    )
    (comp (ref "R41")
      (value "33")
      (footprint "eagle-import:RCL_R0402")
      (libsource (lib "eagle-import") (part "RCL_R-EU_R0402"))
    )
    (comp (ref "R42")
      (value "33")
      (footprint "eagle-import:RCL_R0402")
      (libsource (lib "eagle-import") (part "RCL_R-EU_R0402"))
    )
    (comp (ref "R43")
      (value "33")
      (footprint "eagle-import:RCL_R0402")
      (libsource (lib "eagle-import") (part "RCL_R-EU_R0402"))
    )
    (comp (ref "R44")
      (value "33")
      (footprint "eagle-import:RCL_R0402")
      (libsource (lib "eagle-import") (part "RCL_R-EU_R0402"))
    )
    (comp (ref "R45")
      (value "33")
      (footprint "eagle-import:RCL_R0402")
      (libsource (lib "eagle-import") (part "RCL_R-EU_R0402"))
    )
    (comp (ref "U6")
      (value "CS2100-CP_CS2100-CP-CZZ")
      (footprint "eagle-import:CS2100-CP_CIRRUS-LOGIC_MSOP10")
      (libsource (lib "eagle-import") (part "CS2100-CP_CS2100-CP-CZZ"))
    )
    (comp (ref "Y1")
      (value "ECS-3225Q-33-240-DP-TR_ECS-3225Q-33-240-DP-TR")
      (footprint "eagle-import:ECS-3225Q-33-240-DP-TR_ECS3225Q33240DPTR")
      (fields
        (field (name "MANUFACTURER_PART_NUMBER") "ECS-3225Q-33-240-DP-TR")
        (field (name "MOUSER_PART_NUMBER") "520-3225Q-33-240-DPT")
      )
      (libsource (lib "eagle-import") (part "ECS-3225Q-33-240-DP-TR_ECS-3225Q-33-240-DP-TR"))
    )
  )
  (nets
    (net (code "1") (name "1V0") (class "Default")
      (node (ref "C35") (pin "1") (pinfunction "1_1") (pintype "passive"))
      (node (ref "C37") (pin "1") (pinfunction "1_1") (pintype "passive"))
      (node (ref "C39") (pin "1") (pinfunction "1_1") (pintype "passive"))
      (node (ref "C41") (pin "1") (pinfunction "1_1") (pintype "passive"))
      (node (ref "C43") (pin "1") (pinfunction "1_1") (pintype "passive"))
      (node (ref "C45") (pin "1") (pinfunction "1_1") (pintype "passive"))
      (node (ref "C48") (pin "1") (pinfunction "1_1") (pintype "passive"))
      (node (ref "C50") (pin "1") (pinfunction "1_1") (pintype "passive"))
      (node (ref "C55") (pin "1") (pinfunction "1_1") (pintype "passive"))
      (node (ref "L3") (pin "2") (pinfunction "2_2") (pintype "bidirectional"))
      (node (ref "R16") (pin "2") (pinfunction "2_2") (pintype "passive"))
      (node (ref "R21") (pin "2") (pinfunction "2_2") (pintype "passive"))
      (node (ref "R54") (pin "2") (pinfunction "2_2") (pintype "passive"))
      (node (ref "R56") (pin "2") (pinfunction "2_2") (pintype "passive"))
      (node (ref "U3") (pin "101") (pinfunction "VDD_101") (pintype "power_in"))
      (node (ref "U3") (pin "102") (pinfunction "VDD_102") (pintype "power_in"))
      (node (ref "U3") (pin "11") (pinfunction "VDD_11") (pintype "power_in"))
      (node (ref "U3") (pin "120") (pinfunction "VDD_120") (pintype "power_in"))
      (node (ref "U3") (pin "126") (pinfunction "VDD_126") (pintype "power_in"))
      (node (ref "U3") (pin "16") (pinfunction "VDD_16") (pintype "power_in"))
      (node (ref "U3") (pin "17") (pinfunction "VDD_17") (pintype "power_in"))
      (node (ref "U3") (pin "24") (pinfunction "VDD_24") (pintype "power_in"))
      (node (ref "U3") (pin "36") (pinfunction "VDD_36") (pintype "power_in"))
      (node (ref "U3") (pin "41") (pinfunction "VDD_41") (pintype "power_in"))
      (node (ref "U3") (pin "49") (pinfunction "USB_VDD_49") (pintype "power_in"))
      (node (ref "U3") (pin "56") (pinfunction "VDD_56") (pintype "power_in"))
      (node (ref "U3") (pin "60") (pinfunction "VDD_60") (pintype "power_in"))
      (node (ref "U3") (pin "73") (pinfunction "VDD_73") (pintype "power_in"))
      (node (ref "U3") (pin "80") (pinfunction "VDD_80") (pintype "power_in"))
      (node (ref "U3") (pin "81") (pinfunction "VDD_81") (pintype "power_in"))
      (node (ref "U3") (pin "87") (pinfunction "VDD_87") (pintype "power_in"))
    )
    (net (code "2") (name "1V1") (class "Default")
      (node (ref "C11") (pin "1") (pinfunction "1_1") (pintype "passive"))
      (node (ref "C14") (pin "1") (pinfunction "1_1") (pintype "passive"))
      (node (ref "C17") (pin "1") (pinfunction "1_1") (pintype "passive"))
      (node (ref "FL1") (pin "1") (pinfunction "1_1") (pintype "passive"))
      (node (ref "L1") (pin "2") (pinfunction "2_2") (pintype "passive"))
      (node (ref "U2") (pin "38") (pinfunction "DVDDL_38") (pintype "power_in"))
    )
    (net (code "3") (name "2V5") (class "Default")
      (node (ref "C33") (pin "1") (pinfunction "1_1") (pintype "passive"))
      (node (ref "C54") (pin "1") (pinfunction "1_1") (pintype "passive"))
      (node (ref "U3") (pin "110") (pinfunction "VDDIOT_110") (pintype "power_in"))
      (node (ref "U3") (pin "111") (pinfunction "VDDIOT_111") (pintype "power_in"))
      (node (ref "U9") (pin "4") (pinfunction "OUT_4") (pintype "passive"))
    )
    (net (code "4") (name "3V3") (class "Default")
      (node (ref "C10") (pin "1") (pinfunction "1_1") (pintype "passive"))
      (node (ref "C26") (pin "1") (pinfunction "1_1") (pintype "passive"))
      (node (ref "C27") (pin "1") (pinfunction "1_1") (pintype "passive"))
      (node (ref "C28") (pin "1") (pinfunction "1_1") (pintype "passive"))
      (node (ref "C34") (pin "1") (pinfunction "1_1") (pintype "passive"))
      (node (ref "C36") (pin "1") (pinfunction "1_1") (pintype "passive"))
      (node (ref "C38") (pin "1") (pinfunction "1_1") (pintype "passive"))
      (node (ref "C40") (pin "1") (pinfunction "1_1") (pintype "passive"))
      (node (ref "C42") (pin "1") (pinfunction "1_1") (pintype "passive"))
      (node (ref "C44") (pin "1") (pinfunction "1_1") (pintype "passive"))
      (node (ref "C46") (pin "1") (pinfunction "1_1") (pintype "passive"))
      (node (ref "C47") (pin "1") (pinfunction "1_1") (pintype "passive"))
      (node (ref "C49") (pin "1") (pinfunction "1_1") (pintype "passive"))
      (node (ref "C8") (pin "1") (pinfunction "1_1") (pintype "passive"))
      (node (ref "FL3") (pin "1") (pinfunction "1_1") (pintype "passive"))
      (node (ref "FL4") (pin "1") (pinfunction "1_1") (pintype "passive"))
      (node (ref "IC1") (pin "8") (pinfunction "VCC_8") (pintype "power_in"))
      (node (ref "L2") (pin "2") (pinfunction "2_2") (pintype "bidirectional"))
      (node (ref "R17") (pin "2") (pinfunction "2_2") (pintype "passive"))
      (node (ref "R3") (pin "2") (pinfunction "2_2") (pintype "passive"))
      (node (ref "R34") (pin "2") (pinfunction "2_2") (pintype "passive"))
      (node (ref "R35") (pin "2") (pinfunction "2_2") (pintype "passive"))
      (node (ref "R36") (pin "2") (pinfunction "2_2") (pintype "passive"))
      (node (ref "R37") (pin "2") (pinfunction "2_2") (pintype "passive"))
      (node (ref "R39") (pin "1") (pinfunction "1_1") (pintype "passive"))
      (node (ref "R4") (pin "2") (pinfunction "2_2") (pintype "passive"))
      (node (ref "R40") (pin "1") (pinfunction "1_1") (pintype "passive"))
      (node (ref "R49") (pin "2") (pinfunction "2_2") (pintype "passive"))
      (node (ref "R5") (pin "2") (pinfunction "2_2") (pintype "passive"))
      (node (ref "R51") (pin "2") (pinfunction "2_2") (pintype "passive"))
      (node (ref "R52") (pin "2") (pinfunction "2_2") (pintype "passive"))
      (node (ref "R53") (pin "2") (pinfunction "2_2") (pintype "passive"))
      (node (ref "U2") (pin "3") (pinfunction "VDD33_3") (pintype "power_in"))
      (node (ref "U3") (pin "105") (pinfunction "OTP_VCC_105") (pintype "power_in"))
      (node (ref "U3") (pin "14") (pinfunction "VDDIOL_14") (pintype "power_in"))
      (node (ref "U3") (pin "19") (pinfunction "VDDIOL_19") (pintype "power_in"))
      (node (ref "U3") (pin "29") (pinfunction "VDDIOL_29") (pintype "power_in"))
      (node (ref "U3") (pin "42") (pinfunction "VDDIOL_42") (pintype "power_in"))
      (node (ref "U3") (pin "44") (pinfunction "USB_VDD33_44") (pintype "power_in"))
      (node (ref "U3") (pin "52") (pinfunction "VDDIOR_52") (pintype "power_in"))
      (node (ref "U3") (pin "6") (pinfunction "VDDIOL_6") (pintype "power_in"))
      (node (ref "U3") (pin "67") (pinfunction "VDDIOR_67") (pintype "power_in"))
      (node (ref "U3") (pin "78") (pinfunction "VDDIOR_78") (pintype "power_in"))
      (node (ref "U3") (pin "83") (pinfunction "VDDIOR_83") (pintype "power_in"))
      (node (ref "U3") (pin "92") (pinfunction "VDDIOR_92") (pintype "power_in"))
      (node (ref "U4") (pin "6") (pinfunction "VCC_6") (pintype "power_in"))
      (node (ref "U5") (pin "5") (pinfunction "VCC_5") (pintype "power_in"))
      (node (ref "U8") (pin "2") (pinfunction "IN_2") (pintype "input"))
      (node (ref "X3") (pin "3") (pinfunction "S_3") (pintype "passive"))
      (node (ref "X3") (pin "4") (pinfunction "S_4") (pintype "passive"))
    )
    (net (code "5") (name "3V3A") (class "Default")
      (node (ref "C29") (pin "1") (pinfunction "1_1") (pintype "passive"))
      (node (ref "C31") (pin "1") (pinfunction "1_1") (pintype "passive"))
      (node (ref "FL4") (pin "2") (pinfunction "2_2") (pintype "passive"))
      (node (ref "R38") (pin "1") (pinfunction "1_1") (pintype "passive"))
      (node (ref "U6") (pin "1") (pinfunction "VD_1") (pintype "bidirectional"))
      (node (ref "Y1") (pin "4") (pinfunction "VDD_4") (pintype "bidirectional"))
    )
    (net (code "6") (name "3V3_PG") (class "Default")
      (node (ref "R53") (pin "1") (pinfunction "1_1") (pintype "passive"))
      (node (ref "U10") (pin "6") (pinfunction "EN_6") (pintype "input"))
      (node (ref "U4") (pin "1") (pinfunction "ENIN/~{ENIN}_1") (pintype "input"))
      (node (ref "U8") (pin "1") (pinfunction "~{RST}_1") (pintype "output"))
    )
    (net (code "7") (name "5V0") (class "Default")
      (node (ref "C32") (pin "1") (pinfunction "1_1") (pintype "passive"))
      (node (ref "C52") (pin "1") (pinfunction "1_1") (pintype "passive"))
      (node (ref "C53") (pin "1") (pinfunction "1_1") (pintype "passive"))
      (node (ref "FL2") (pin "1") (pinfunction "1_1") (pintype "bidirectional"))
      (node (ref "U10") (pin "4") (pinfunction "VIN_SW_4") (pintype "input"))
      (node (ref "U10") (pin "5") (pinfunction "VIN_A_5") (pintype "input"))
      (node (ref "U7") (pin "4") (pinfunction "VIN_SW_4") (pintype "input"))
      (node (ref "U7") (pin "5") (pinfunction "VIN_A_5") (pintype "input"))
      (node (ref "U7") (pin "6") (pinfunction "EN_6") (pintype "input"))
      (node (ref "U9") (pin "1") (pinfunction "EN_1") (pintype "input"))
      (node (ref "U9") (pin "5") (pinfunction "IN_5") (pintype "input"))
      (node (ref "X3") (pin "1") (pinfunction "S_1") (pintype "passive"))
      (node (ref "X3") (pin "2") (pinfunction "S_2") (pintype "passive"))
    )
    (net (code "8") (name "24M_CLK") (class "Default")
      (node (ref "R42") (pin "2") (pinfunction "2_2") (pintype "passive"))
      (node (ref "U3") (pin "125") (pinfunction "CLK_125") (pintype "input"))
    )
    (net (code "9") (name "ADC_RST_N") (class "Default")
      (node (ref "R31") (pin "1") (pinfunction "1_1") (pintype "passive"))
      (node (ref "U3") (pin "95") (pinfunction "X0D32_95") (pintype "bidirectional"))
    )
    (net (code "10") (name "ADC_RST_N_OUT") (class "Default")
      (node (ref "R31") (pin "2") (pinfunction "2_2") (pintype "passive"))
      (node (ref "X3") (pin "6") (pinfunction "S_6") (pintype "passive"))
    )
    (net (code "11") (name "AVDD33") (class "Default")
      (node (ref "C13") (pin "1") (pinfunction "1_1") (pintype "passive"))
      (node (ref "C18") (pin "1") (pinfunction "1_1") (pintype "passive"))
      (node (ref "FL3") (pin "2") (pinfunction "2_2") (pintype "passive"))
      (node (ref "U2") (pin "14") (pinfunction "AVDD33_14") (pintype "power_in"))
    )
    (net (code "12") (name "AVDDL") (class "Default")
      (node (ref "C12") (pin "1") (pinfunction "1_1") (pintype "passive"))
      (node (ref "C15") (pin "1") (pinfunction "1_1") (pintype "passive"))
      (node (ref "C20") (pin "1") (pinfunction "1_1") (pintype "passive"))
      (node (ref "FL1") (pin "2") (pinfunction "2_2") (pintype "passive"))
      (node (ref "U2") (pin "11") (pinfunction "AVDDL_11") (pintype "power_in"))
      (node (ref "U2") (pin "17") (pinfunction "AVDDL_17") (pintype "power_in"))
      (node (ref "U2") (pin "6") (pinfunction "AVDDL_6") (pintype "power_in"))
    )
    (net (code "13") (name "GND") (class "Default")
      (node (ref "C1") (pin "1") (pinfunction "1_1") (pintype "passive"))
      (node (ref "C10") (pin "2") (pinfunction "2_2") (pintype "passive"))
      (node (ref "C11") (pin "2") (pinfunction "2_2") (pintype "passive"))
      (node (ref "C12") (pin "2") (pinfunction "2_2") (pintype "passive"))
      (node (ref "C13") (pin "2") (pinfunction "2_2") (pintype "passive"))
      (node (ref "C14") (pin "2") (pinfunction "2_2") (pintype "passive"))
      (node (ref "C15") (pin "2") (pinfunction "2_2") (pintype "passive"))
      (node (ref "C16") (pin "2") (pinfunction "2_2") (pintype "passive"))
      (node (ref "C17") (pin "2") (pinfunction "2_2") (pintype "passive"))
      (node (ref "C18") (pin "2") (pinfunction "2_2") (pintype "passive"))
      (node (ref "C19") (pin "2") (pinfunction "2_2") (pintype "passive"))
      (node (ref "C2") (pin "1") (pinfunction "1_1") (pintype "passive"))
      (node (ref "C20") (pin "2") (pinfunction "2_2") (pintype "passive"))
      (node (ref "C21") (pin "2") (pinfunction "2_2") (pintype "passive"))
      (node (ref "C22") (pin "2") (pinfunction "2_2") (pintype "passive"))
      (node (ref "C23") (pin "2") (pinfunction "2_2") (pintype "passive"))
      (node (ref "C24") (pin "2") (pinfunction "2_2") (pintype "passive"))
      (node (ref "C25") (pin "2") (pinfunction "2_2") (pintype "passive"))
      (node (ref "C26") (pin "2") (pinfunction "2_2") (pintype "passive"))
      (node (ref "C27") (pin "2") (pinfunction "2_2") (pintype "passive"))
      (node (ref "C28") (pin "2") (pinfunction "2_2") (pintype "passive"))
      (node (ref "C29") (pin "2") (pinfunction "2_2") (pintype "passive"))
      (node (ref "C3") (pin "1") (pinfunction "1_1") (pintype "passive"))
      (node (ref "C30") (pin "2") (pinfunction "2_2") (pintype "passive"))
      (node (ref "C31") (pin "2") (pinfunction "2_2") (pintype "passive"))
      (node (ref "C32") (pin "2") (pinfunction "2_2") (pintype "passive"))
      (node (ref "C33") (pin "2") (pinfunction "2_2") (pintype "passive"))
      (node (ref "C34") (pin "2") (pinfunction "2_2") (pintype "passive"))
      (node (ref "C35") (pin "2") (pinfunction "2_2") (pintype "passive"))
      (node (ref "C36") (pin "2") (pinfunction "2_2") (pintype "passive"))
      (node (ref "C37") (pin "2") (pinfunction "2_2") (pintype "passive"))
      (node (ref "C38") (pin "2") (pinfunction "2_2") (pintype "passive"))
      (node (ref "C39") (pin "2") (pinfunction "2_2") (pintype "passive"))
      (node (ref "C4") (pin "1") (pinfunction "1_1") (pintype "passive"))
      (node (ref "C40") (pin "2") (pinfunction "2_2") (pintype "passive"))
      (node (ref "C41") (pin "2") (pinfunction "2_2") (pintype "passive"))
      (node (ref "C42") (pin "2") (pinfunction "2_2") (pintype "passive"))
      (node (ref "C43") (pin "2") (pinfunction "2_2") (pintype "passive"))
      (node (ref "C44") (pin "2") (pinfunction "2_2") (pintype "passive"))
      (node (ref "C45") (pin "2") (pinfunction "2_2") (pintype "passive"))
      (node (ref "C46") (pin "2") (pinfunction "2_2") (pintype "passive"))
      (node (ref "C47") (pin "2") (pinfunction "2_2") (pintype "passive"))
      (node (ref "C48") (pin "2") (pinfunction "2_2") (pintype "passive"))
      (node (ref "C49") (pin "2") (pinfunction "2_2") (pintype "passive"))
      (node (ref "C5") (pin "2") (pinfunction "2_2") (pintype "passive"))
      (node (ref "C50") (pin "2") (pinfunction "2_2") (pintype "passive"))
      (node (ref "C51") (pin "2") (pinfunction "2_2") (pintype "passive"))
      (node (ref "C52") (pin "2") (pinfunction "2_2") (pintype "passive"))
      (node (ref "C53") (pin "2") (pinfunction "2_2") (pintype "passive"))
      (node (ref "C54") (pin "2") (pinfunction "2_2") (pintype "passive"))
      (node (ref "C55") (pin "2") (pinfunction "2_2") (pintype "passive"))
      (node (ref "C56") (pin "2") (pinfunction "2_2") (pintype "passive"))
      (node (ref "C57") (pin "2") (pinfunction "2_2") (pintype "passive"))
      (node (ref "C58") (pin "2") (pinfunction "2_2") (pintype "passive"))
      (node (ref "C6") (pin "2") (pinfunction "2_2") (pintype "passive"))
      (node (ref "C7") (pin "2") (pinfunction "2_2") (pintype "passive"))
      (node (ref "C8") (pin "2") (pinfunction "2_2") (pintype "passive"))
      (node (ref "C9") (pin "2") (pinfunction "2_2") (pintype "passive"))
      (node (ref "IC1") (pin "4") (pinfunction "GND_4") (pintype "power_in"))
      (node (ref "J3") (pin "10") (pinfunction "10_10") (pintype "bidirectional"))
      (node (ref "J3") (pin "18") (pinfunction "18_18") (pintype "bidirectional"))
      (node (ref "J3") (pin "3") (pinfunction "3_3") (pintype "bidirectional"))
      (node (ref "LED1") (pin "C") (pinfunction "C_C") (pintype "passive"))
      (node (ref "LED2") (pin "C") (pinfunction "C_C") (pintype "passive"))
      (node (ref "R1") (pin "1") (pinfunction "1_1") (pintype "passive"))
      (node (ref "R11") (pin "1") (pinfunction "1_1") (pintype "passive"))
      (node (ref "R18") (pin "1") (pinfunction "1_1") (pintype "passive"))
      (node (ref "R2") (pin "1") (pinfunction "1_1") (pintype "passive"))
      (node (ref "R22") (pin "1") (pinfunction "1_1") (pintype "passive"))
      (node (ref "R50") (pin "1") (pinfunction "1_1") (pintype "passive"))
      (node (ref "R51") (pin "1") (pinfunction "1_1") (pintype "passive"))
      (node (ref "R55") (pin "1") (pinfunction "1_1") (pintype "passive"))
      (node (ref "R56") (pin "1") (pinfunction "1_1") (pintype "passive"))
      (node (ref "R9") (pin "1") (pinfunction "1_1") (pintype "passive"))
      (node (ref "U1") (pin "3") (pinfunction "-VDC_3") (pintype "bidirectional"))
      (node (ref "U10") (pin "2") (pinfunction "GND_2") (pintype "power_in"))
      (node (ref "U10") (pin "7") (pinfunction "GND_7") (pintype "power_in"))
      (node (ref "U2") (pin "41") (pinfunction "GND_41") (pintype "power_in"))
      (node (ref "U3") (pin "104") (pinfunction "PLL_AGND_104") (pintype "power_in"))
      (node (ref "U3") (pin "129") (pinfunction "GND_129") (pintype "power_in"))
      (node (ref "U4") (pin "2") (pinfunction "GND_2") (pintype "power_in"))
      (node (ref "U5") (pin "2") (pinfunction "GND_2") (pintype "passive"))
      (node (ref "U6") (pin "2") (pinfunction "GND_2") (pintype "bidirectional"))
      (node (ref "U6") (pin "8") (pinfunction "AD0/N_CS_8") (pintype "bidirectional"))
      (node (ref "U7") (pin "2") (pinfunction "GND_2") (pintype "power_in"))
      (node (ref "U7") (pin "7") (pinfunction "GND_7") (pintype "power_in"))
      (node (ref "U8") (pin "3") (pinfunction "GND_3") (pintype "input"))
      (node (ref "U9") (pin "3") (pinfunction "GND_3") (pintype "power_in"))
      (node (ref "X1") (pin "2") (pinfunction "GND2_2") (pintype "passive"))
      (node (ref "X1") (pin "4") (pinfunction "GND4_4") (pintype "passive"))
      (node (ref "X3") (pin "10") (pinfunction "S_10") (pintype "passive"))
      (node (ref "X3") (pin "12") (pinfunction "S_12") (pintype "passive"))
      (node (ref "X3") (pin "14") (pinfunction "S_14") (pintype "passive"))
      (node (ref "X3") (pin "16") (pinfunction "S_16") (pintype "passive"))
      (node (ref "X3") (pin "18") (pinfunction "S_18") (pintype "passive"))
      (node (ref "X3") (pin "20") (pinfunction "S_20") (pintype "passive"))
      (node (ref "X3") (pin "22") (pinfunction "S_22") (pintype "passive"))
      (node (ref "X3") (pin "25") (pinfunction "S_25") (pintype "passive"))
      (node (ref "X3") (pin "26") (pinfunction "S_26") (pintype "passive"))
      (node (ref "X3") (pin "28") (pinfunction "S_28") (pintype "passive"))
      (node (ref "X3") (pin "30") (pinfunction "S_30") (pintype "passive"))
      (node (ref "X3") (pin "8") (pinfunction "S_8") (pintype "passive"))
      (node (ref "Y1") (pin "2") (pinfunction "GND_2") (pintype "bidirectional"))
    )
    (net (code "14") (name "GND_2") (class "Default")
      (node (ref "IC1") (pin "9") (pinfunction "GND_2_9") (pintype "power_in"))
    )
    (net (code "15") (name "GPIO_IN") (class "Default")
      (node (ref "R46") (pin "2") (pinfunction "2_2") (pintype "passive"))
      (node (ref "X3") (pin "7") (pinfunction "S_7") (pintype "passive"))
    )
    (net (code "16") (name "GPIO_OUT") (class "Default")
      (node (ref "LED1") (pin "A") (pinfunction "A_A") (pintype "passive"))
      (node (ref "R30") (pin "1") (pinfunction "1_1") (pintype "passive"))
      (node (ref "X3") (pin "5") (pinfunction "S_5") (pintype "passive"))
    )
    (net (code "17") (name "LRCK_OUT") (class "Default")
      (node (ref "R26") (pin "2") (pinfunction "2_2") (pintype "passive"))
      (node (ref "X3") (pin "19") (pinfunction "S_19") (pintype "passive"))
    )
    (net (code "18") (name "LRCLK") (class "Default")
      (node (ref "R26") (pin "1") (pinfunction "1_1") (pintype "passive"))
      (node (ref "U3") (pin "64") (pinfunction "X0D22_64") (pintype "bidirectional"))
    )
    (net (code "19") (name "MCLK_AUDIO") (class "Default")
      (node (ref "R43") (pin "2") (pinfunction "2_2") (pintype "passive"))
      (node (ref "X3") (pin "21") (pinfunction "S_21") (pintype "passive"))
    )
    (net (code "20") (name "MCLK_OUT") (class "Default")
      (node (ref "R43") (pin "1") (pinfunction "1_1") (pintype "passive"))
      (node (ref "R44") (pin "1") (pinfunction "1_1") (pintype "passive"))
      (node (ref "R45") (pin "2") (pinfunction "2_2") (pintype "passive"))
      (node (ref "U6") (pin "3") (pinfunction "CLK_OUT_3") (pintype "bidirectional"))
    )
    (net (code "21") (name "MCLK_XCORE0") (class "Default")
      (node (ref "R45") (pin "1") (pinfunction "1_1") (pintype "passive"))
      (node (ref "U3") (pin "63") (pinfunction "X0D13_63") (pintype "bidirectional"))
    )
    (net (code "22") (name "MCLK_XCORE1") (class "Default")
      (node (ref "R44") (pin "2") (pinfunction "2_2") (pintype "passive"))
      (node (ref "U3") (pin "13") (pinfunction "X1D35_13") (pintype "bidirectional"))
    )
    (net (code "23") (name "Net-(IC1-IO0)") (class "Default")
      (node (ref "IC1") (pin "5") (pinfunction "IO0_5") (pintype "bidirectional"))
      (node (ref "U3") (pin "31") (pinfunction "X0D04_31") (pintype "bidirectional"))
    )
    (net (code "24") (name "Net-(IC1-IO1)") (class "Default")
      (node (ref "IC1") (pin "2") (pinfunction "IO1_2") (pintype "bidirectional"))
      (node (ref "U3") (pin "33") (pinfunction "X0D05_33") (pintype "bidirectional"))
    )
    (net (code "25") (name "Net-(IC1-IO2)") (class "Default")
      (node (ref "IC1") (pin "3") (pinfunction "IO2_3") (pintype "bidirectional"))
      (node (ref "U3") (pin "34") (pinfunction "X0D06_34") (pintype "bidirectional"))
    )
    (net (code "26") (name "Net-(IC1-IO3)") (class "Default")
      (node (ref "IC1") (pin "7") (pinfunction "IO3_7") (pintype "bidirectional"))
      (node (ref "U3") (pin "35") (pinfunction "X0D07_35") (pintype "bidirectional"))
    )
    (net (code "27") (name "Net-(IC1-SCK)") (class "Default")
      (node (ref "IC1") (pin "6") (pinfunction "SCK_6") (pintype "input"))
      (node (ref "U3") (pin "28") (pinfunction "X0D10_28") (pintype "bidirectional"))
    )
    (net (code "28") (name "Net-(IC1-~{CE})") (class "Default")
      (node (ref "IC1") (pin "1") (pinfunction "~{CE}_1") (pintype "input"))
      (node (ref "R35") (pin "1") (pinfunction "1_1") (pintype "passive"))
      (node (ref "U3") (pin "27") (pinfunction "X0D01_27") (pintype "bidirectional"))
    )
    (net (code "29") (name "Net-(J1-GREEN_A{slash}K)") (class "Default")
      (node (ref "C6") (pin "1") (pinfunction "1_1") (pintype "passive"))
      (node (ref "J1") (pin "19") (pinfunction "GREEN_A/K_19") (pintype "bidirectional"))
      (node (ref "R4") (pin "1") (pinfunction "1_1") (pintype "passive"))
      (node (ref "R7") (pin "1") (pinfunction "1_1") (pintype "passive"))
      (node (ref "U2") (pin "24") (pinfunction "LED_10_100_24") (pintype "bidirectional"))
    )
    (net (code "30") (name "Net-(J1-GREEN_K{slash}A)") (class "Default")
      (node (ref "C5") (pin "1") (pinfunction "1_1") (pintype "passive"))
      (node (ref "J1") (pin "20") (pinfunction "GREEN_K/A_20") (pintype "bidirectional"))
      (node (ref "R5") (pin "1") (pinfunction "1_1") (pintype "passive"))
      (node (ref "R6") (pin "1") (pinfunction "1_1") (pintype "passive"))
      (node (ref "U2") (pin "22") (pinfunction "LED_1000_22") (pintype "bidirectional"))
    )
    (net (code "31") (name "Net-(J1-PadMH1)") (class "Default")
      (node (ref "J1") (pin "MH1") (pinfunction "MH1_MH1") (pintype "bidirectional"))
      (node (ref "R1") (pin "2") (pinfunction "2_2") (pintype "passive"))
    )
    (net (code "32") (name "Net-(J1-PadMH2)") (class "Default")
      (node (ref "J1") (pin "MH2") (pinfunction "MH2_MH2") (pintype "bidirectional"))
      (node (ref "R2") (pin "2") (pinfunction "2_2") (pintype "passive"))
    )
    (net (code "33") (name "Net-(J1-TRCT1)") (class "Default")
      (node (ref "C1") (pin "2") (pinfunction "2_2") (pintype "passive"))
      (node (ref "J1") (pin "12") (pinfunction "TRCT1_12") (pintype "bidirectional"))
    )
    (net (code "34") (name "Net-(J1-TRCT2)") (class "Default")
      (node (ref "C2") (pin "2") (pinfunction "2_2") (pintype "passive"))
      (node (ref "J1") (pin "6") (pinfunction "TRCT2_6") (pintype "bidirectional"))
    )
    (net (code "35") (name "Net-(J1-TRCT3)") (class "Default")
      (node (ref "C3") (pin "2") (pinfunction "2_2") (pintype "passive"))
      (node (ref "J1") (pin "1") (pinfunction "TRCT3_1") (pintype "bidirectional"))
    )
    (net (code "36") (name "Net-(J1-TRCT4)") (class "Default")
      (node (ref "C4") (pin "2") (pinfunction "2_2") (pintype "passive"))
      (node (ref "J1") (pin "7") (pinfunction "TRCT4_7") (pintype "bidirectional"))
    )
    (net (code "37") (name "Net-(J1-YELLOW_A)") (class "Default")
      (node (ref "J1") (pin "18") (pinfunction "YELLOW_A_18") (pintype "bidirectional"))
      (node (ref "R3") (pin "1") (pinfunction "1_1") (pintype "passive"))
    )
    (net (code "38") (name "Net-(J1-YELLOW_K)") (class "Default")
      (node (ref "C7") (pin "1") (pinfunction "1_1") (pintype "passive"))
      (node (ref "J1") (pin "17") (pinfunction "YELLOW_K_17") (pintype "bidirectional"))
      (node (ref "R10") (pin "1") (pinfunction "1_1") (pintype "passive"))
      (node (ref "U2") (pin "21") (pinfunction "LED_ACT_21") (pintype "bidirectional"))
    )
    (net (code "39") (name "Net-(LED2-PadA)") (class "Default")
      (node (ref "LED2") (pin "A") (pinfunction "A_A") (pintype "passive"))
      (node (ref "R52") (pin "1") (pinfunction "1_1") (pintype "passive"))
    )
    (net (code "40") (name "Net-(U1-ADJ)") (class "Default")
      (node (ref "R8") (pin "1") (pinfunction "1_1") (pintype "passive"))
      (node (ref "R9") (pin "2") (pinfunction "2_2") (pintype "passive"))
      (node (ref "U1") (pin "4") (pinfunction "ADJ_4") (pintype "bidirectional"))
    )
    (net (code "41") (name "Net-(U2-LX)") (class "Default")
      (node (ref "L1") (pin "1") (pinfunction "1_1") (pintype "passive"))
      (node (ref "U2") (pin "2") (pinfunction "LX_2") (pintype "output"))
    )
    (net (code "42") (name "Net-(U2-RBIAS)") (class "Default")
      (node (ref "R11") (pin "2") (pinfunction "2_2") (pintype "passive"))
      (node (ref "U2") (pin "7") (pinfunction "RBIAS_7") (pintype "output"))
    )
    (net (code "43") (name "Net-(U2-RX_CLK)") (class "Default")
      (node (ref "R12") (pin "1") (pinfunction "1_1") (pintype "passive"))
      (node (ref "U2") (pin "31") (pinfunction "RX_CLK_31") (pintype "bidirectional"))
    )
    (net (code "44") (name "Net-(U2-XTLI)") (class "Default")
      (node (ref "C22") (pin "1") (pinfunction "1_1") (pintype "passive"))
      (node (ref "U2") (pin "5") (pinfunction "XTLI_5") (pintype "input"))
      (node (ref "X1") (pin "1") (pinfunction "1_1") (pintype "passive"))
    )
    (net (code "45") (name "Net-(U2-XTLO)") (class "Default")
      (node (ref "C21") (pin "1") (pinfunction "1_1") (pintype "passive"))
      (node (ref "U2") (pin "4") (pinfunction "XTLO_4") (pintype "output"))
      (node (ref "X1") (pin "3") (pinfunction "3_3") (pintype "passive"))
    )
    (net (code "46") (name "Net-(U3-TRST_N)") (class "Default")
      (node (ref "R23") (pin "2") (pinfunction "2_2") (pintype "passive"))
      (node (ref "U3") (pin "123") (pinfunction "TRST_N_123") (pintype "input"))
    )
    (net (code "47") (name "Net-(U3-X0D30)") (class "Default")
      (node (ref "R30") (pin "2") (pinfunction "2_2") (pintype "passive"))
      (node (ref "U3") (pin "99") (pinfunction "X0D30_99") (pintype "bidirectional"))
    )
    (net (code "48") (name "Net-(U3-X0D42)") (class "Default")
      (node (ref "R24") (pin "1") (pinfunction "1_1") (pintype "passive"))
      (node (ref "U3") (pin "10") (pinfunction "X0D42_10") (pintype "bidirectional"))
    )
    (net (code "49") (name "Net-(U3-X0D43)") (class "Default")
      (node (ref "R25") (pin "1") (pinfunction "1_1") (pintype "passive"))
      (node (ref "U3") (pin "12") (pinfunction "X0D43_12") (pintype "bidirectional"))
    )
    (net (code "50") (name "Net-(U3-X1D26)") (class "Default")
      (node (ref "R20") (pin "2") (pinfunction "2_2") (pintype "passive"))
      (node (ref "U3") (pin "112") (pinfunction "X1D26_112") (pintype "bidirectional"))
    )
    (net (code "51") (name "Net-(U4-CEXT)") (class "Default")
      (node (ref "C25") (pin "1") (pinfunction "1_1") (pintype "passive"))
      (node (ref "U4") (pin "5") (pinfunction "CEXT_5") (pintype "passive"))
    )
    (net (code "52") (name "Net-(U4-VIN)") (class "Default")
      (node (ref "R21") (pin "1") (pinfunction "1_1") (pintype "passive"))
      (node (ref "R22") (pin "2") (pinfunction "2_2") (pintype "passive"))
      (node (ref "U4") (pin "3") (pinfunction "VIN_3") (pintype "input"))
    )
    (net (code "53") (name "Net-(U6-XTI{slash}REF_CLK)") (class "Default")
      (node (ref "R41") (pin "2") (pinfunction "2_2") (pintype "passive"))
      (node (ref "U6") (pin "7") (pinfunction "XTI/REF_CLK_7") (pintype "bidirectional"))
    )
    (net (code "54") (name "Net-(U7-FB)") (class "Default")
      (node (ref "R49") (pin "1") (pinfunction "1_1") (pintype "passive"))
      (node (ref "R50") (pin "2") (pinfunction "2_2") (pintype "passive"))
      (node (ref "U7") (pin "1") (pinfunction "FB_1") (pintype "input"))
    )
    (net (code "55") (name "Net-(U7-SW)") (class "Default")
      (node (ref "L2") (pin "1") (pinfunction "1_1") (pintype "bidirectional"))
      (node (ref "U7") (pin "3") (pinfunction "SW_3") (pintype "output"))
    )
    (net (code "56") (name "Net-(U8-CD)") (class "Default")
      (node (ref "C51") (pin "1") (pinfunction "1_1") (pintype "passive"))
      (node (ref "U8") (pin "5") (pinfunction "CD_5") (pintype "passive"))
    )
    (net (code "57") (name "Net-(U10-FB)") (class "Default")
      (node (ref "R54") (pin "1") (pinfunction "1_1") (pintype "passive"))
      (node (ref "R55") (pin "2") (pinfunction "2_2") (pintype "passive"))
      (node (ref "U10") (pin "1") (pinfunction "FB_1") (pintype "input"))
    )
    (net (code "58") (name "Net-(U10-SW)") (class "Default")
      (node (ref "L3") (pin "1") (pinfunction "1_1") (pintype "bidirectional"))
      (node (ref "U10") (pin "3") (pinfunction "SW_3") (pintype "output"))
    )
    (net (code "59") (name "Net-(Y1-OUTPUT)") (class "Default")
      (node (ref "R41") (pin "1") (pinfunction "1_1") (pintype "passive"))
      (node (ref "R42") (pin "1") (pinfunction "1_1") (pintype "passive"))
      (node (ref "Y1") (pin "3") (pinfunction "OUTPUT_3") (pintype "bidirectional"))
    )
    (net (code "60") (name "Net-(Y1-TRI-STATE)") (class "Default")
      (node (ref "R38") (pin "2") (pinfunction "2_2") (pintype "passive"))
      (node (ref "Y1") (pin "1") (pinfunction "TRI-STATE_1") (pintype "bidirectional"))
    )
    (net (code "61") (name "PHY_INT") (class "Default")
      (node (ref "R17") (pin "1") (pinfunction "1_1") (pintype "passive"))
      (node (ref "U2") (pin "20") (pinfunction "INT_20") (pintype "bidirectional"))
      (node (ref "U3") (pin "74") (pinfunction "X1D03_74") (pintype "bidirectional"))
    )
    (net (code "62") (name "PHY_MDC") (class "Default")
      (node (ref "U2") (pin "40") (pinfunction "MDC_40") (pintype "input"))
      (node (ref "U3") (pin "122") (pinfunction "X1D11_122") (pintype "bidirectional"))
    )
    (net (code "63") (name "PHY_MDIO") (class "Default")
      (node (ref "R15") (pin "1") (pinfunction "1_1") (pintype "passive"))
      (node (ref "U2") (pin "39") (pinfunction "MDIO_39") (pintype "bidirectional"))
      (node (ref "U3") (pin "121") (pinfunction "X1D10_121") (pintype "bidirectional"))
    )
    (net (code "64") (name "PHY_RSTN") (class "Default")
      (node (ref "C24") (pin "1") (pinfunction "1_1") (pintype "passive"))
      (node (ref "R18") (pin "2") (pinfunction "2_2") (pintype "passive"))
      (node (ref "U2") (pin "1") (pinfunction "RSTN_1") (pintype "input"))
      (node (ref "U3") (pin "72") (pinfunction "X1D02_72") (pintype "bidirectional"))
    )
    (net (code "65") (name "PLL_AVDD") (class "Default")
      (node (ref "C23") (pin "1") (pinfunction "1_1") (pintype "passive"))
      (node (ref "R16") (pin "1") (pinfunction "1_1") (pintype "passive"))
      (node (ref "U3") (pin "103") (pinfunction "PLL_AVDD_103") (pintype "power_in"))
    )
    (net (code "66") (name "PLL_SYNC") (class "Default")
      (node (ref "U3") (pin "30") (pinfunction "X0D00_30") (pintype "bidirectional"))
      (node (ref "U6") (pin "5") (pinfunction "CLK_IN_5") (pintype "bidirectional"))
    )
    (net (code "67") (name "POR_N") (class "Default")
      (node (ref "R34") (pin "1") (pinfunction "1_1") (pintype "passive"))
      (node (ref "U4") (pin "4") (pinfunction "EOUT/~{EOUT}_4") (pintype "output"))
      (node (ref "U5") (pin "1") (pinfunction "A1_1") (pintype "input"))
    )
    (net (code "68") (name "RST_N") (class "Default")
      (node (ref "R23") (pin "1") (pinfunction "1_1") (pintype "passive"))
      (node (ref "R37") (pin "1") (pinfunction "1_1") (pintype "passive"))
      (node (ref "U3") (pin "124") (pinfunction "RST_N_124") (pintype "input"))
      (node (ref "U5") (pin "4") (pinfunction "Y2_4") (pintype "output"))
      (node (ref "U5") (pin "6") (pinfunction "Y1_6") (pintype "output"))
    )
    (net (code "69") (name "RX_CLK") (class "Default")
      (node (ref "R12") (pin "2") (pinfunction "2_2") (pintype "passive"))
      (node (ref "U3") (pin "114") (pinfunction "X1D28_114") (pintype "bidirectional"))
    )
    (net (code "70") (name "RX_D0") (class "Default")
      (node (ref "U2") (pin "29") (pinfunction "RXD0_29") (pintype "bidirectional"))
      (node (ref "U3") (pin "116") (pinfunction "X1D30_116") (pintype "bidirectional"))
    )
    (net (code "71") (name "RX_D1") (class "Default")
      (node (ref "U2") (pin "28") (pinfunction "RXD1_28") (pintype "bidirectional"))
      (node (ref "U3") (pin "117") (pinfunction "X1D31_117") (pintype "bidirectional"))
    )
    (net (code "72") (name "RX_D2") (class "Default")
      (node (ref "R13") (pin "1") (pinfunction "1_1") (pintype "passive"))
      (node (ref "U2") (pin "26") (pinfunction "RXD2_26") (pintype "bidirectional"))
      (node (ref "U3") (pin "118") (pinfunction "X1D32_118") (pintype "bidirectional"))
    )
    (net (code "73") (name "RX_D3") (class "Default")
      (node (ref "R14") (pin "1") (pinfunction "1_1") (pintype "passive"))
      (node (ref "U2") (pin "25") (pinfunction "RXD3_25") (pintype "bidirectional"))
      (node (ref "U3") (pin "119") (pinfunction "X1D33_119") (pintype "bidirectional"))
    )
    (net (code "74") (name "RX_DV") (class "Default")
      (node (ref "U2") (pin "30") (pinfunction "RX_DV_30") (pintype "bidirectional"))
      (node (ref "U3") (pin "115") (pinfunction "X1D29_115") (pintype "bidirectional"))
    )
    (net (code "75") (name "SCL") (class "Default")
      (node (ref "R40") (pin "2") (pinfunction "2_2") (pintype "passive"))
      (node (ref "U3") (pin "37") (pinfunction "X0D02_37") (pintype "bidirectional"))
      (node (ref "U6") (pin "9") (pinfunction "SCL/CCLK_9") (pintype "bidirectional"))
      (node (ref "X3") (pin "24") (pinfunction "S_24") (pintype "passive"))
    )
    (net (code "76") (name "SCLK") (class "Default")
      (node (ref "R27") (pin "1") (pinfunction "1_1") (pintype "passive"))
      (node (ref "U3") (pin "66") (pinfunction "X0D23_66") (pintype "bidirectional"))
    )
    (net (code "77") (name "SCLK_OUT") (class "Default")
      (node (ref "R27") (pin "2") (pinfunction "2_2") (pintype "passive"))
      (node (ref "X3") (pin "17") (pinfunction "S_17") (pintype "passive"))
    )
    (net (code "78") (name "SDA") (class "Default")
      (node (ref "R39") (pin "2") (pinfunction "2_2") (pintype "passive"))
      (node (ref "U3") (pin "38") (pinfunction "X0D03_38") (pintype "bidirectional"))
      (node (ref "U6") (pin "10") (pinfunction "SDA/CDIN_10") (pintype "bidirectional"))
      (node (ref "X3") (pin "23") (pinfunction "S_23") (pintype "passive"))
    )
    (net (code "79") (name "SDIOA") (class "Default")
      (node (ref "R28") (pin "1") (pinfunction "1_1") (pintype "passive"))
      (node (ref "U3") (pin "88") (pinfunction "X0D24_88") (pintype "bidirectional"))
    )
    (net (code "80") (name "SDIOA_OUT") (class "Default")
      (node (ref "R28") (pin "2") (pinfunction "2_2") (pintype "passive"))
      (node (ref "X3") (pin "15") (pinfunction "S_15") (pintype "passive"))
    )
    (net (code "81") (name "SDIOB") (class "Default")
      (node (ref "R29") (pin "1") (pinfunction "1_1") (pintype "passive"))
      (node (ref "U3") (pin "89") (pinfunction "X0D25_89") (pintype "bidirectional"))
    )
    (net (code "82") (name "SDIOB_I2S_OUT") (class "Default")
      (node (ref "R29") (pin "2") (pinfunction "2_2") (pintype "passive"))
      (node (ref "X3") (pin "13") (pinfunction "S_13") (pintype "passive"))
    )
    (net (code "83") (name "SDIOC") (class "Default")
      (node (ref "R32") (pin "1") (pinfunction "1_1") (pintype "passive"))
      (node (ref "U3") (pin "90") (pinfunction "X0D34_90") (pintype "bidirectional"))
    )
    (net (code "84") (name "SDIOC_IN") (class "Default")
      (node (ref "R32") (pin "2") (pinfunction "2_2") (pintype "passive"))
      (node (ref "X3") (pin "11") (pinfunction "S_11") (pintype "passive"))
    )
    (net (code "85") (name "SDIOD") (class "Default")
      (node (ref "R33") (pin "1") (pinfunction "1_1") (pintype "passive"))
      (node (ref "U3") (pin "91") (pinfunction "X0D35_91") (pintype "bidirectional"))
    )
    (net (code "86") (name "SDIOD_I2S_IN") (class "Default")
      (node (ref "R33") (pin "2") (pinfunction "2_2") (pintype "passive"))
      (node (ref "X3") (pin "9") (pinfunction "S_9") (pintype "passive"))
    )
    (net (code "87") (name "SDIOE_OUT") (class "Default")
      (node (ref "R47") (pin "2") (pinfunction "2_2") (pintype "passive"))
      (node (ref "X3") (pin "27") (pinfunction "S_27") (pintype "passive"))
    )
    (net (code "88") (name "SDIOF_IN") (class "Default")
      (node (ref "R48") (pin "2") (pinfunction "2_2") (pintype "passive"))
      (node (ref "X3") (pin "29") (pinfunction "S_29") (pintype "passive"))
    )
    (net (code "89") (name "TCK") (class "Default")
      (node (ref "J3") (pin "13") (pinfunction "13_13") (pintype "bidirectional"))
      (node (ref "U3") (pin "128") (pinfunction "TCK_128") (pintype "input"))
    )
    (net (code "90") (name "TDI") (class "Default")
      (node (ref "J3") (pin "15") (pinfunction "15_15") (pintype "bidirectional"))
      (node (ref "U3") (pin "2") (pinfunction "TDI_2") (pintype "input"))
    )
    (net (code "91") (name "TDO") (class "Default")
      (node (ref "J3") (pin "14") (pinfunction "14_14") (pintype "bidirectional"))
      (node (ref "U3") (pin "1") (pinfunction "TDO_1") (pintype "output"))
    )
    (net (code "92") (name "TMS") (class "Default")
      (node (ref "J3") (pin "12") (pinfunction "12_12") (pintype "bidirectional"))
      (node (ref "U3") (pin "127") (pinfunction "TMS_127") (pintype "input"))
    )
    (net (code "93") (name "TRD1_N") (class "Default")
      (node (ref "J1") (pin "10") (pinfunction "TRD1-_10") (pintype "bidirectional"))
      (node (ref "U2") (pin "10") (pinfunction "TRXN0_10") (pintype "output"))
    )
    (net (code "94") (name "TRD1_P") (class "Default")
      (node (ref "J1") (pin "11") (pinfunction "TRD1+_11") (pintype "bidirectional"))
      (node (ref "U2") (pin "9") (pinfunction "TRXP0_9") (pintype "input"))
    )
    (net (code "95") (name "TRD2_N") (class "Default")
      (node (ref "J1") (pin "5") (pinfunction "TRD2-_5") (pintype "bidirectional"))
      (node (ref "U2") (pin "13") (pinfunction "TRXN1_13") (pintype "output"))
    )
    (net (code "96") (name "TRD2_P") (class "Default")
      (node (ref "J1") (pin "4") (pinfunction "TRD2+_4") (pintype "bidirectional"))
      (node (ref "U2") (pin "12") (pinfunction "TRXP1_12") (pintype "input"))
    )
    (net (code "97") (name "TRD3_N") (class "Default")
      (node (ref "J1") (pin "2") (pinfunction "TRD3-_2") (pintype "bidirectional"))
      (node (ref "U2") (pin "16") (pinfunction "TRXN2_16") (pintype "output"))
    )
    (net (code "98") (name "TRD3_P") (class "Default")
      (node (ref "J1") (pin "3") (pinfunction "TRD3+_3") (pintype "bidirectional"))
      (node (ref "U2") (pin "15") (pinfunction "TRXP2_15") (pintype "input"))
    )
    (net (code "99") (name "TRD4_N") (class "Default")
      (node (ref "J1") (pin "9") (pinfunction "TRD4-_9") (pintype "bidirectional"))
      (node (ref "U2") (pin "19") (pinfunction "TRXN3_19") (pintype "output"))
    )
    (net (code "100") (name "TRD4_P") (class "Default")
      (node (ref "J1") (pin "8") (pinfunction "TRD4+_8") (pintype "bidirectional"))
      (node (ref "U2") (pin "18") (pinfunction "TRXP3_18") (pintype "input"))
    )
    (net (code "101") (name "TX_CLK") (class "Default")
      (node (ref "R20") (pin "1") (pinfunction "1_1") (pintype "passive"))
      (node (ref "U2") (pin "33") (pinfunction "GTX_CLK_33") (pintype "input"))
    )
    (net (code "102") (name "TX_D0") (class "Default")
      (node (ref "U2") (pin "34") (pinfunction "TXD0_34") (pintype "input"))
      (node (ref "U3") (pin "109") (pinfunction "X1D43_109") (pintype "bidirectional"))
    )
    (net (code "103") (name "TX_D1") (class "Default")
      (node (ref "U2") (pin "35") (pinfunction "TXD1_35") (pintype "input"))
      (node (ref "U3") (pin "108") (pinfunction "X1D42_108") (pintype "bidirectional"))
    )
    (net (code "104") (name "TX_D2") (class "Default")
      (node (ref "U2") (pin "36") (pinfunction "TXD2_36") (pintype "input"))
      (node (ref "U3") (pin "107") (pinfunction "X1D41_107") (pintype "bidirectional"))
    )
    (net (code "105") (name "TX_D3") (class "Default")
      (node (ref "U2") (pin "37") (pinfunction "TXD3_37") (pintype "input"))
      (node (ref "U3") (pin "106") (pinfunction "X1D40_106") (pintype "bidirectional"))
    )
    (net (code "106") (name "TX_EN") (class "Default")
      (node (ref "U2") (pin "32") (pinfunction "TX_EN_32") (pintype "input"))
      (node (ref "U3") (pin "113") (pinfunction "X1D27_113") (pintype "bidirectional"))
    )
    (net (code "107") (name "VC1+") (class "Default")
      (node (ref "B1") (pin "+") (pinfunction "+_+") (pintype "passive"))
      (node (ref "B2") (pin "+") (pinfunction "+_+") (pintype "passive"))
      (node (ref "U1") (pin "5") (pinfunction "VIN+_1_5") (pintype "bidirectional"))
      (node (ref "U1") (pin "6") (pinfunction "VIN+_2_6") (pintype "bidirectional"))
    )
    (net (code "108") (name "VC1-") (class "Default")
      (node (ref "B1") (pin "-") (pinfunction "-_-") (pintype "passive"))
      (node (ref "B2") (pin "-") (pinfunction "-_-") (pintype "passive"))
      (node (ref "U1") (pin "7") (pinfunction "VIN-_1_7") (pintype "bidirectional"))
      (node (ref "U1") (pin "8") (pinfunction "VIN-_2_8") (pintype "bidirectional"))
    )
    (net (code "109") (name "VC12") (class "Default")
      (node (ref "B2") (pin "~1") (pinfunction "AC1_~1") (pintype "passive"))
      (node (ref "J1") (pin "13") (pinfunction "VC12_13") (pintype "bidirectional"))
      (node (ref "JP1") (pin "1") (pinfunction "1_1") (pintype "passive"))
    )
    (net (code "110") (name "VC36") (class "Default")
      (node (ref "B2") (pin "~2") (pinfunction "AC2_~2") (pintype "passive"))
      (node (ref "J1") (pin "14") (pinfunction "VC36_14") (pintype "bidirectional"))
      (node (ref "JP1") (pin "2") (pinfunction "2_2") (pintype "passive"))
    )
    (net (code "111") (name "VC45") (class "Default")
      (node (ref "B1") (pin "~1") (pinfunction "AC1_~1") (pintype "passive"))
      (node (ref "J1") (pin "15") (pinfunction "VC45_15") (pintype "bidirectional"))
      (node (ref "JP1") (pin "4") (pinfunction "4_4") (pintype "passive"))
    )
    (net (code "112") (name "VC78") (class "Default")
      (node (ref "B1") (pin "~2") (pinfunction "AC2_~2") (pintype "passive"))
      (node (ref "J1") (pin "16") (pinfunction "VC78_16") (pintype "bidirectional"))
      (node (ref "JP1") (pin "3") (pinfunction "3_3") (pintype "passive"))
    )
    (net (code "113") (name "VDC") (class "Default")
      (node (ref "C30") (pin "1") (pinfunction "1_1") (pintype "passive"))
      (node (ref "C56") (pin "1") (pinfunction "1_1") (pintype "passive"))
      (node (ref "C57") (pin "1") (pinfunction "1_1") (pintype "passive"))
      (node (ref "C58") (pin "1") (pinfunction "1_1") (pintype "passive"))
      (node (ref "C9") (pin "1") (pinfunction "1_1") (pintype "passive"))
      (node (ref "FL2") (pin "2") (pinfunction "2_2") (pintype "bidirectional"))
      (node (ref "R8") (pin "2") (pinfunction "2_2") (pintype "passive"))
      (node (ref "U1") (pin "1") (pinfunction "+VDC_1_1") (pintype "bidirectional"))
      (node (ref "U1") (pin "2") (pinfunction "+VDC_2_2") (pintype "bidirectional"))
    )
    (net (code "114") (name "VDDH_REG") (class "Default")
      (node (ref "C16") (pin "1") (pinfunction "1_1") (pintype "passive"))
      (node (ref "C19") (pin "1") (pinfunction "1_1") (pintype "passive"))
      (node (ref "R10") (pin "2") (pinfunction "2_2") (pintype "passive"))
      (node (ref "R13") (pin "2") (pinfunction "2_2") (pintype "passive"))
      (node (ref "R14") (pin "2") (pinfunction "2_2") (pintype "passive"))
      (node (ref "R15") (pin "2") (pinfunction "2_2") (pintype "passive"))
      (node (ref "R6") (pin "2") (pinfunction "2_2") (pintype "passive"))
      (node (ref "R7") (pin "2") (pinfunction "2_2") (pintype "passive"))
      (node (ref "U2") (pin "27") (pinfunction "VDDIO_REG_27") (pintype "output"))
      (node (ref "U2") (pin "8") (pinfunction "VDDH_REG_8") (pintype "output"))
    )
    (net (code "115") (name "X1D04") (class "Default")
      (node (ref "R46") (pin "1") (pinfunction "1_1") (pintype "passive"))
      (node (ref "U3") (pin "75") (pinfunction "X1D04_75") (pintype "bidirectional"))
    )
    (net (code "116") (name "X1D36") (class "Default")
      (node (ref "R48") (pin "1") (pinfunction "1_1") (pintype "passive"))
      (node (ref "U3") (pin "15") (pinfunction "X1D36_15") (pintype "bidirectional"))
    )
    (net (code "117") (name "X1D37") (class "Default")
      (node (ref "R47") (pin "1") (pinfunction "1_1") (pintype "passive"))
      (node (ref "U3") (pin "18") (pinfunction "X1D37_18") (pintype "bidirectional"))
    )
    (net (code "118") (name "XL_DN0") (class "Default")
      (node (ref "J3") (pin "7") (pinfunction "7_7") (pintype "bidirectional"))
      (node (ref "U3") (pin "9") (pinfunction "X0D41_9") (pintype "bidirectional"))
    )
    (net (code "119") (name "XL_DN1") (class "Default")
      (node (ref "J3") (pin "6") (pinfunction "6_6") (pintype "bidirectional"))
      (node (ref "U3") (pin "8") (pinfunction "X0D40_8") (pintype "bidirectional"))
    )
    (net (code "120") (name "XL_UP0") (class "Default")
      (node (ref "J3") (pin "8") (pinfunction "8_8") (pintype "bidirectional"))
      (node (ref "R24") (pin "2") (pinfunction "2_2") (pintype "passive"))
    )
    (net (code "121") (name "XL_UP1") (class "Default")
      (node (ref "J3") (pin "9") (pinfunction "9_9") (pintype "bidirectional"))
      (node (ref "R25") (pin "2") (pinfunction "2_2") (pintype "passive"))
    )
    (net (code "122") (name "XSYS_RST_N") (class "Default")
      (node (ref "J3") (pin "11") (pinfunction "11_11") (pintype "bidirectional"))
      (node (ref "R36") (pin "1") (pinfunction "1_1") (pintype "passive"))
      (node (ref "U5") (pin "3") (pinfunction "A2_3") (pintype "input"))
    )
    (net (code "123") (name "unconnected-(J3-Pad1)") (class "Default")
      (node (ref "J3") (pin "1") (pinfunction "1_1") (pintype "bidirectional"))
    )
    (net (code "124") (name "unconnected-(J3-Pad2)") (class "Default")
      (node (ref "J3") (pin "2") (pinfunction "2_2") (pintype "bidirectional"))
    )
    (net (code "125") (name "unconnected-(J3-Pad4)") (class "Default")
      (node (ref "J3") (pin "4") (pinfunction "4_4") (pintype "bidirectional"))
    )
    (net (code "126") (name "unconnected-(J3-Pad5)") (class "Default")
      (node (ref "J3") (pin "5") (pinfunction "5_5") (pintype "bidirectional"))
    )
    (net (code "127") (name "unconnected-(J3-Pad16)") (class "Default")
      (node (ref "J3") (pin "16") (pinfunction "16_16") (pintype "bidirectional"))
    )
    (net (code "128") (name "unconnected-(J3-Pad17)") (class "Default")
      (node (ref "J3") (pin "17") (pinfunction "17_17") (pintype "bidirectional"))
    )
    (net (code "129") (name "unconnected-(J3-Pad19)") (class "Default")
      (node (ref "J3") (pin "19") (pinfunction "19_19") (pintype "bidirectional"))
    )
    (net (code "130") (name "unconnected-(J3-Pad20)") (class "Default")
      (node (ref "J3") (pin "20") (pinfunction "20_20") (pintype "bidirectional"))
    )
    (net (code "131") (name "unconnected-(U2-CLK_25M-Pad23)") (class "Default")
      (node (ref "U2") (pin "23") (pinfunction "CLK_25M_23") (pintype "output"))
    )
    (net (code "132") (name "unconnected-(U3-USB_DM-Pad47)") (class "Default")
      (node (ref "U3") (pin "47") (pinfunction "USB_DM_47") (pintype "bidirectional"))
    )
    (net (code "133") (name "unconnected-(U3-USB_DP-Pad46)") (class "Default")
      (node (ref "U3") (pin "46") (pinfunction "USB_DP_46") (pintype "bidirectional"))
    )
    (net (code "134") (name "unconnected-(U3-USB_ID-Pad43)") (class "Default")
      (node (ref "U3") (pin "43") (pinfunction "USB_ID_43") (pintype "bidirectional"))
    )
    (net (code "135") (name "unconnected-(U3-USB_RTUNE-Pad48)") (class "Default")
      (node (ref "U3") (pin "48") (pinfunction "USB_RTUNE_48") (pintype "bidirectional"))
    )
    (net (code "136") (name "unconnected-(U3-USB_VBUS-Pad45)") (class "Default")
      (node (ref "U3") (pin "45") (pinfunction "USB_VBUS_45") (pintype "bidirectional"))
    )
    (net (code "137") (name "unconnected-(U3-X0D08-Pad39)") (class "Default")
      (node (ref "U3") (pin "39") (pinfunction "X0D08_39") (pintype "bidirectional"))
    )
    (net (code "138") (name "unconnected-(U3-X0D09-Pad40)") (class "Default")
      (node (ref "U3") (pin "40") (pinfunction "X0D09_40") (pintype "bidirectional"))
    )
    (net (code "139") (name "unconnected-(U3-X0D11-Pad32)") (class "Default")
      (node (ref "U3") (pin "32") (pinfunction "X0D11_32") (pintype "bidirectional"))
    )
    (net (code "140") (name "unconnected-(U3-X0D12-Pad62)") (class "Default")
      (node (ref "U3") (pin "62") (pinfunction "X0D12_62") (pintype "bidirectional"))
    )
    (net (code "141") (name "unconnected-(U3-X0D14-Pad57)") (class "Default")
      (node (ref "U3") (pin "57") (pinfunction "X0D14_57") (pintype "bidirectional"))
    )
    (net (code "142") (name "unconnected-(U3-X0D15-Pad58)") (class "Default")
      (node (ref "U3") (pin "58") (pinfunction "X0D15_58") (pintype "bidirectional"))
    )
    (net (code "143") (name "unconnected-(U3-X0D16-Pad68)") (class "Default")
      (node (ref "U3") (pin "68") (pinfunction "X0D16_68") (pintype "bidirectional"))
    )
    (net (code "144") (name "unconnected-(U3-X0D17-Pad69)") (class "Default")
      (node (ref "U3") (pin "69") (pinfunction "X0D17_69") (pintype "bidirectional"))
    )
    (net (code "145") (name "unconnected-(U3-X0D18-Pad70)") (class "Default")
      (node (ref "U3") (pin "70") (pinfunction "X0D18_70") (pintype "bidirectional"))
    )
    (net (code "146") (name "unconnected-(U3-X0D19-Pad71)") (class "Default")
      (node (ref "U3") (pin "71") (pinfunction "X0D19_71") (pintype "bidirectional"))
    )
    (net (code "147") (name "unconnected-(U3-X0D20-Pad59)") (class "Default")
      (node (ref "U3") (pin "59") (pinfunction "X0D20_59") (pintype "bidirectional"))
    )
    (net (code "148") (name "unconnected-(U3-X0D21-Pad61)") (class "Default")
      (node (ref "U3") (pin "61") (pinfunction "X0D21_61") (pintype "bidirectional"))
    )
    (net (code "149") (name "unconnected-(U3-X0D26-Pad93)") (class "Default")
      (node (ref "U3") (pin "93") (pinfunction "X0D26_93") (pintype "bidirectional"))
    )
    (net (code "150") (name "unconnected-(U3-X0D27-Pad94)") (class "Default")
      (node (ref "U3") (pin "94") (pinfunction "X0D27_94") (pintype "bidirectional"))
    )
    (net (code "151") (name "unconnected-(U3-X0D28-Pad96)") (class "Default")
      (node (ref "U3") (pin "96") (pinfunction "X0D28_96") (pintype "bidirectional"))
    )
    (net (code "152") (name "unconnected-(U3-X0D29-Pad98)") (class "Default")
      (node (ref "U3") (pin "98") (pinfunction "X0D29_98") (pintype "bidirectional"))
    )
    (net (code "153") (name "unconnected-(U3-X0D31-Pad100)") (class "Default")
      (node (ref "U3") (pin "100") (pinfunction "X0D31_100") (pintype "bidirectional"))
    )
    (net (code "154") (name "unconnected-(U3-X0D33-Pad97)") (class "Default")
      (node (ref "U3") (pin "97") (pinfunction "X0D33_97") (pintype "bidirectional"))
    )
    (net (code "155") (name "unconnected-(U3-X0D36-Pad3)") (class "Default")
      (node (ref "U3") (pin "3") (pinfunction "X0D36_3") (pintype "bidirectional"))
    )
    (net (code "156") (name "unconnected-(U3-X0D37-Pad4)") (class "Default")
      (node (ref "U3") (pin "4") (pinfunction "X0D37_4") (pintype "bidirectional"))
    )
    (net (code "157") (name "unconnected-(U3-X0D38-Pad5)") (class "Default")
      (node (ref "U3") (pin "5") (pinfunction "X0D38_5") (pintype "bidirectional"))
    )
    (net (code "158") (name "unconnected-(U3-X0D39-Pad7)") (class "Default")
      (node (ref "U3") (pin "7") (pinfunction "X0D39_7") (pintype "bidirectional"))
    )
    (net (code "159") (name "unconnected-(U3-X1D00-Pad85)") (class "Default")
      (node (ref "U3") (pin "85") (pinfunction "X1D00_85") (pintype "bidirectional"))
    )
    (net (code "160") (name "unconnected-(U3-X1D01-Pad86)") (class "Default")
      (node (ref "U3") (pin "86") (pinfunction "X1D01_86") (pintype "bidirectional"))
    )
    (net (code "161") (name "unconnected-(U3-X1D05-Pad76)") (class "Default")
      (node (ref "U3") (pin "76") (pinfunction "X1D05_76") (pintype "bidirectional"))
    )
    (net (code "162") (name "unconnected-(U3-X1D06-Pad77)") (class "Default")
      (node (ref "U3") (pin "77") (pinfunction "X1D06_77") (pintype "bidirectional"))
    )
    (net (code "163") (name "unconnected-(U3-X1D07-Pad79)") (class "Default")
      (node (ref "U3") (pin "79") (pinfunction "X1D07_79") (pintype "bidirectional"))
    )
    (net (code "164") (name "unconnected-(U3-X1D08-Pad82)") (class "Default")
      (node (ref "U3") (pin "82") (pinfunction "X1D08_82") (pintype "bidirectional"))
    )
    (net (code "165") (name "unconnected-(U3-X1D09-Pad84)") (class "Default")
      (node (ref "U3") (pin "84") (pinfunction "X1D09_84") (pintype "bidirectional"))
    )
    (net (code "166") (name "unconnected-(U3-X1D14-Pad51)") (class "Default")
      (node (ref "U3") (pin "51") (pinfunction "X1D14_51") (pintype "bidirectional"))
    )
    (net (code "167") (name "unconnected-(U3-X1D15-Pad53)") (class "Default")
      (node (ref "U3") (pin "53") (pinfunction "X1D15_53") (pintype "bidirectional"))
    )
    (net (code "168") (name "unconnected-(U3-X1D16-Pad22)") (class "Default")
      (node (ref "U3") (pin "22") (pinfunction "X1D16_22") (pintype "bidirectional"))
    )
    (net (code "169") (name "unconnected-(U3-X1D17-Pad23)") (class "Default")
      (node (ref "U3") (pin "23") (pinfunction "X1D17_23") (pintype "bidirectional"))
    )
    (net (code "170") (name "unconnected-(U3-X1D18-Pad25)") (class "Default")
      (node (ref "U3") (pin "25") (pinfunction "X1D18_25") (pintype "bidirectional"))
    )
    (net (code "171") (name "unconnected-(U3-X1D19-Pad26)") (class "Default")
      (node (ref "U3") (pin "26") (pinfunction "X1D19_26") (pintype "bidirectional"))
    )
    (net (code "172") (name "unconnected-(U3-X1D20-Pad54)") (class "Default")
      (node (ref "U3") (pin "54") (pinfunction "X1D20_54") (pintype "bidirectional"))
    )
    (net (code "173") (name "unconnected-(U3-X1D21-Pad55)") (class "Default")
      (node (ref "U3") (pin "55") (pinfunction "X1D21_55") (pintype "bidirectional"))
    )
    (net (code "174") (name "unconnected-(U3-X1D38-Pad20)") (class "Default")
      (node (ref "U3") (pin "20") (pinfunction "X1D38_20") (pintype "bidirectional"))
    )
    (net (code "175") (name "unconnected-(U3-X1D39-Pad21)") (class "Default")
      (node (ref "U3") (pin "21") (pinfunction "X1D39_21") (pintype "bidirectional"))
    )
    (net (code "176") (name "unconnected-(U6-AUX_OUT-Pad4)") (class "Default")
      (node (ref "U6") (pin "4") (pinfunction "AUX_OUT_4") (pintype "bidirectional"))
    )
    (net (code "177") (name "unconnected-(U6-XTO-Pad6)") (class "Default")
      (node (ref "U6") (pin "6") (pinfunction "XTO_6") (pintype "bidirectional"))
    )
  )
)
